# BoardB-FPGA.net
KiCad netlist of a schematic drawn in Altium Designer
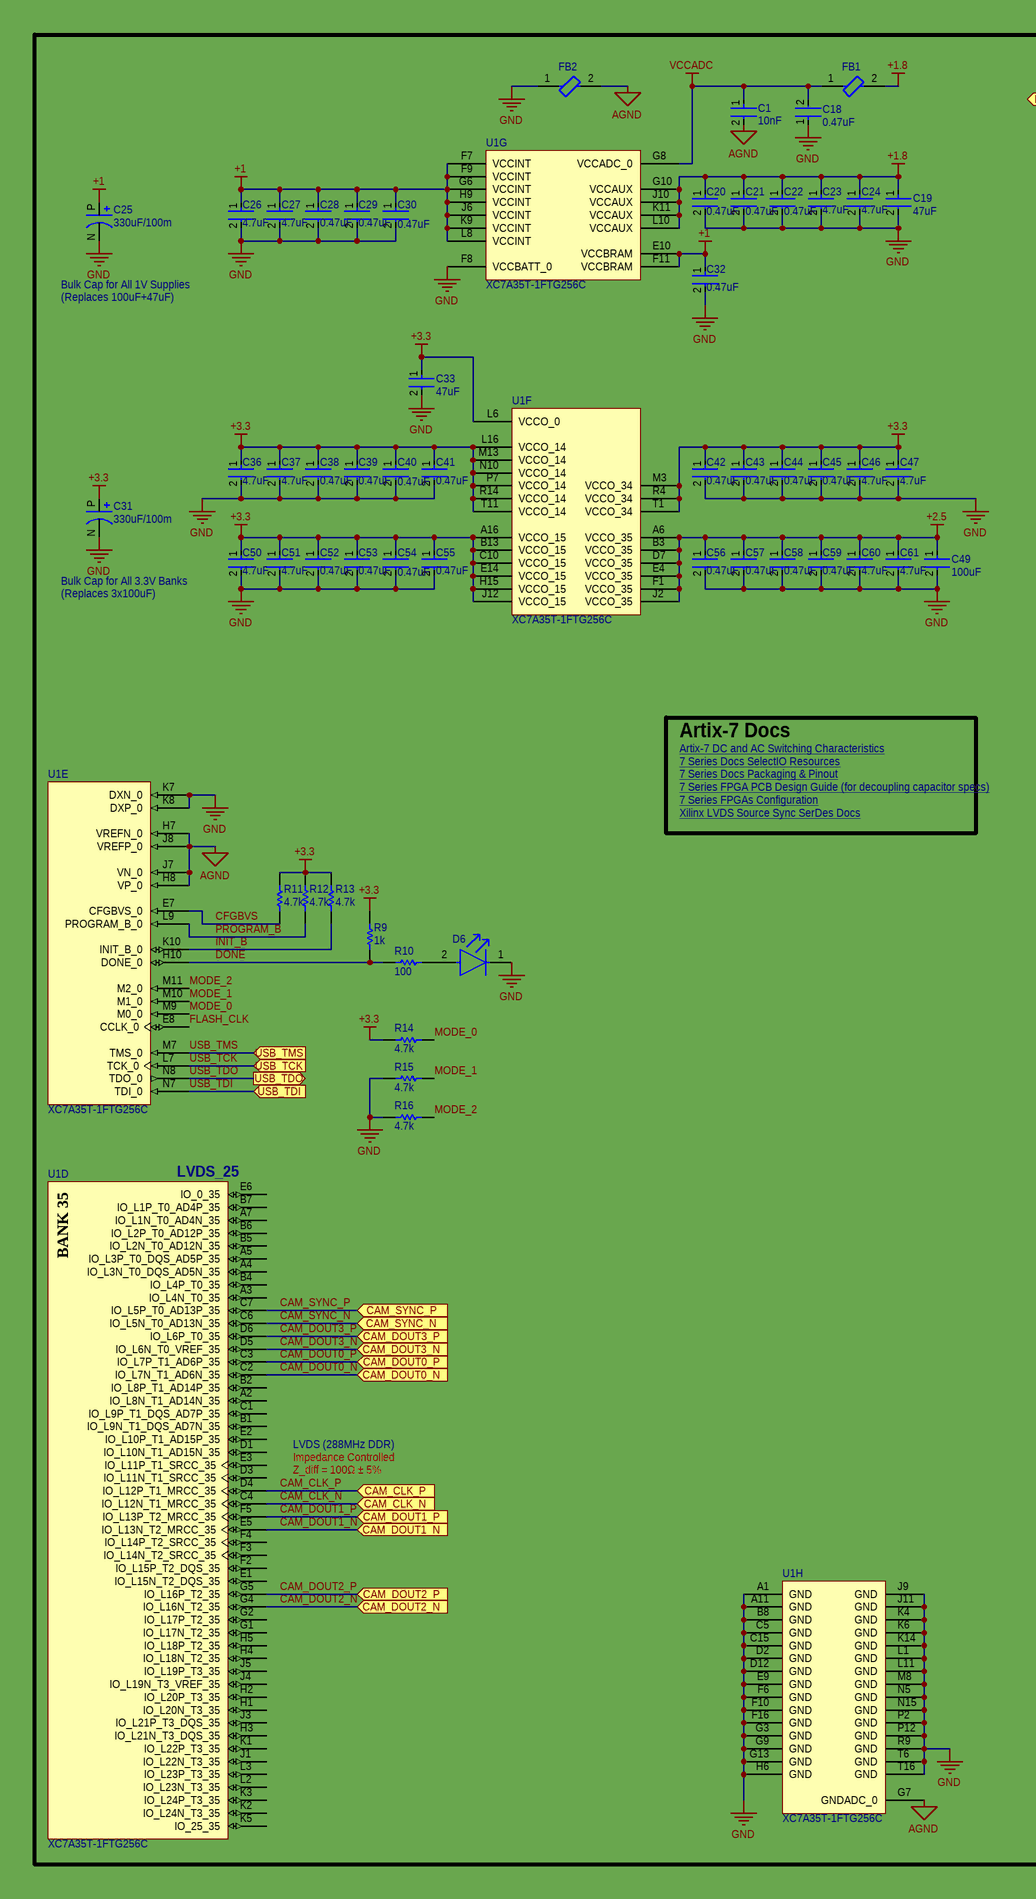
[diagram p0: BoardB-FPGA.SchDoc, left]
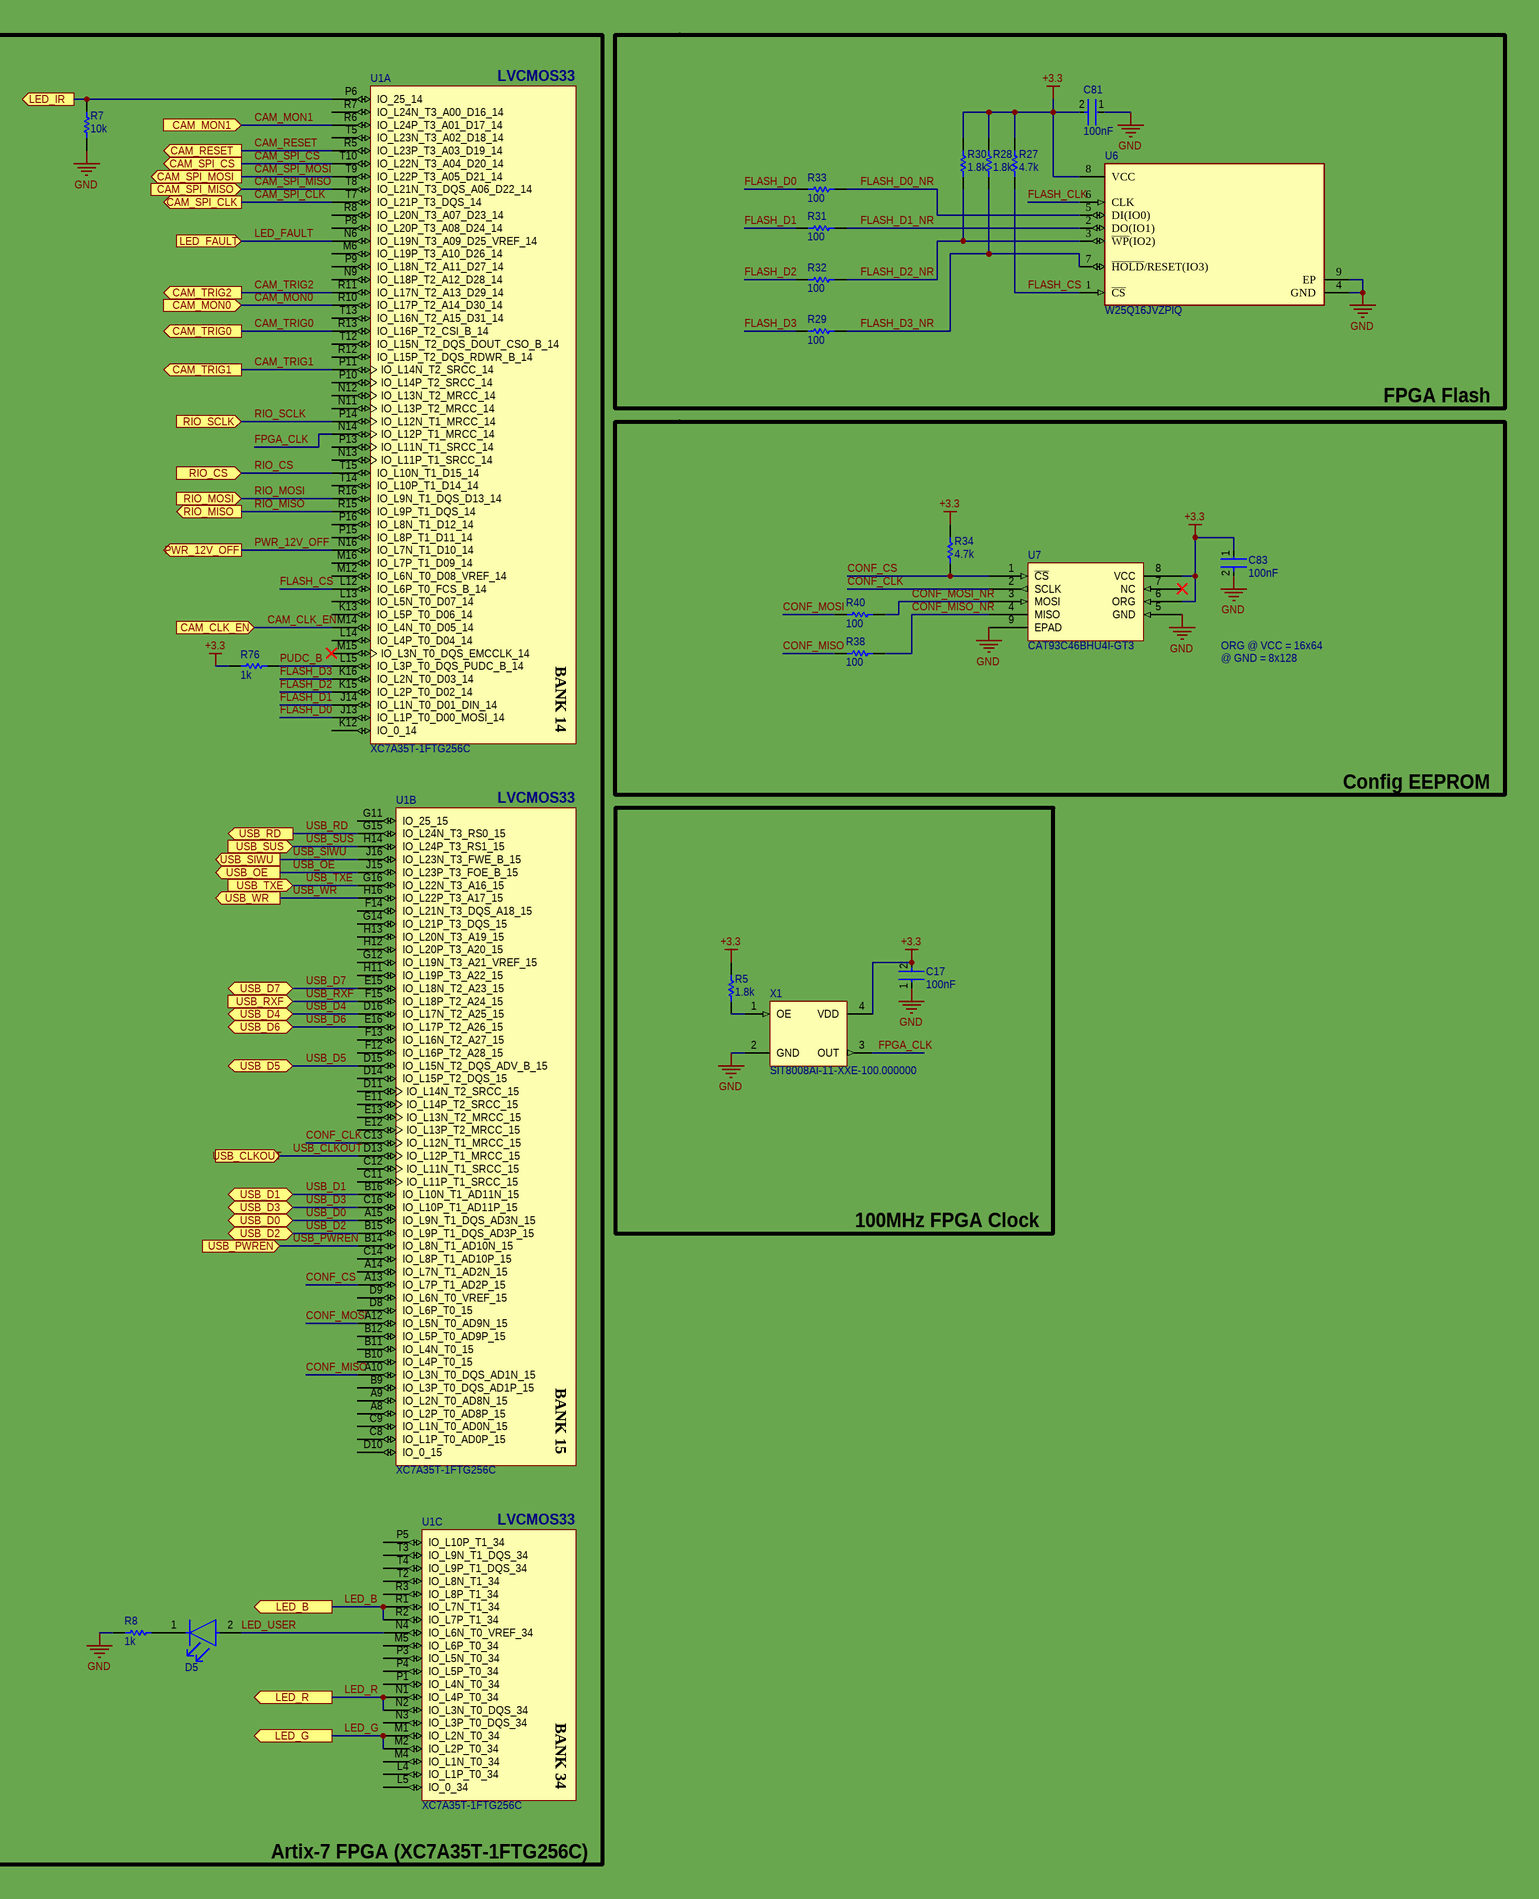
[diagram p1: BoardB-FPGA.SchDoc, right]

(export (version "E")
  (design (tool "Eeschema 10.0.6"))
  (components
    (comp (ref "C1")
      (value "10nF")
      (footprint "FP-GRM033-0_03-IPC_C")
      (description "Chip Multilayer Ceramic Capacitors for General Purpose, 0201, 10000pF, X7R, 15%, 10%, 10V")
      (fields (field (name "VOLTAGE") "10V") (field (name "TOLERANCE") "10%"))
      (libsource (lib "Altium Content Vault") (part "b4654b650e69147ec39a6b967a45e02"))
    )
    (comp (ref "C17")
      (value "100nF")
      (footprint "FP-GRM15-IPC_C")
      (description "CAP CER 0.1UF 16V X7R 0402")
      (fields (field (name "MANUFACTURER PART NUMBER") "GRM155R71C104KA88D") (field (name "TOLERANCE") "10%"))
      (libsource (lib "Altium Content Vault") (part "236180d848d6139a670b325ea6854c9"))
    )
    (comp (ref "C18")
      (value "0.47uF")
      (footprint "FP-GRM033-0_03-IPC_C")
      (description "Chip Multilayer Ceramic Capacitors for General Purpose, 0201, 0.47uF, X5R, 15%, 10%, 6.3V")
      (fields (field (name "TOLERANCE") "10%"))
      (libsource (lib "Altium Content Vault") (part "b4654b650e69147ec39a6b967a45e02"))
    )
    (comp (ref "C19")
      (value "47uF")
      (footprint "FP-GRM188-0_2-MFG")
      (description "Chip Multilayer Ceramic Capacitors for General Purpose, 0603, 47uF, X5R, 15%, 20%, 6.3V")
      (fields (field (name "TOLERANCE") "20%"))
      (libsource (lib "Altium Content Vault") (part "11868f565c42a9108669ba33697ecf6"))
    )
    (comp (ref "C20")
      (value "0.47uF")
      (footprint "FP-GRM033-0_03-IPC_C")
      (description "Chip Multilayer Ceramic Capacitors for General Purpose, 0201, 0.47uF, X5R, 15%, 10%, 6.3V")
      (fields (field (name "TOLERANCE") "10%"))
      (libsource (lib "Altium Content Vault") (part "b4654b650e69147ec39a6b967a45e02"))
    )
    (comp (ref "C21")
      (value "0.47uF")
      (footprint "FP-GRM033-0_03-IPC_C")
      (description "Chip Multilayer Ceramic Capacitors for General Purpose, 0201, 0.47uF, X5R, 15%, 10%, 6.3V")
      (fields (field (name "TOLERANCE") "10%"))
      (libsource (lib "Altium Content Vault") (part "b4654b650e69147ec39a6b967a45e02"))
    )
    (comp (ref "C22")
      (value "0.47uF")
      (footprint "FP-GRM033-0_03-IPC_C")
      (description "Chip Multilayer Ceramic Capacitors for General Purpose, 0201, 0.47uF, X5R, 15%, 10%, 6.3V")
      (fields (field (name "TOLERANCE") "10%"))
      (libsource (lib "Altium Content Vault") (part "b4654b650e69147ec39a6b967a45e02"))
    )
    (comp (ref "C23")
      (value "4.7uF")
      (footprint "FP-GRM155-0_1-IPC_B")
      (description "Chip Multilayer Ceramic Capacitors for General Purpose, 0402, 4.7uF, X5R, 15%, 20%, 6.3V")
      (fields (field (name "VOLTAGE") "6.3V") (field (name "TOLERANCE") "20%"))
      (libsource (lib "Altium Content Vault") (part "11868f565c42a9108669ba33697ecf6"))
    )
    (comp (ref "C24")
      (value "4.7uF")
      (footprint "FP-GRM155-0_1-IPC_B")
      (description "Chip Multilayer Ceramic Capacitors for General Purpose, 0402, 4.7uF, X5R, 15%, 20%, 6.3V")
      (fields (field (name "VOLTAGE") "6.3V") (field (name "TOLERANCE") "20%"))
      (libsource (lib "Altium Content Vault") (part "11868f565c42a9108669ba33697ecf6"))
    )
    (comp (ref "C25")
      (value "330uF/100m")
      (footprint "NOSD337M004R0100")
      (description "330uF +/-20% 4 V dc SMD Niobium Capacitor; 7343-31 package; ESR 0.1Ohms NOS")
      (fields
        (field (name "MANUFACTURER") "Kyocera AVX")
        (field (name "MANUFACTURER PART NUMBER") "NOSD337M004R0100")
      )
      (libsource (lib "Virtex") (part "NOSD337M004R0100"))
    )
    (comp (ref "C26")
      (value "4.7uF")
      (footprint "FP-GRM155-0_1-IPC_B")
      (description "Chip Multilayer Ceramic Capacitors for General Purpose, 0402, 4.7uF, X5R, 15%, 20%, 6.3V")
      (fields (field (name "VOLTAGE") "6.3V") (field (name "TOLERANCE") "20%"))
      (libsource (lib "Altium Content Vault") (part "11868f565c42a9108669ba33697ecf6"))
    )
    (comp (ref "C27")
      (value "4.7uF")
      (footprint "FP-GRM155-0_1-IPC_B")
      (description "Chip Multilayer Ceramic Capacitors for General Purpose, 0402, 4.7uF, X5R, 15%, 20%, 6.3V")
      (fields (field (name "VOLTAGE") "6.3V") (field (name "TOLERANCE") "20%"))
      (libsource (lib "Altium Content Vault") (part "11868f565c42a9108669ba33697ecf6"))
    )
    (comp (ref "C28")
      (value "0.47uF")
      (footprint "FP-GRM033-0_03-IPC_C")
      (description "Chip Multilayer Ceramic Capacitors for General Purpose, 0201, 0.47uF, X5R, 15%, 10%, 6.3V")
      (fields (field (name "TOLERANCE") "10%"))
      (libsource (lib "Altium Content Vault") (part "b4654b650e69147ec39a6b967a45e02"))
    )
    (comp (ref "C29")
      (value "0.47uF")
      (footprint "FP-GRM033-0_03-IPC_C")
      (description "Chip Multilayer Ceramic Capacitors for General Purpose, 0201, 0.47uF, X5R, 15%, 10%, 6.3V")
      (fields (field (name "TOLERANCE") "10%"))
      (libsource (lib "Altium Content Vault") (part "b4654b650e69147ec39a6b967a45e02"))
    )
    (comp (ref "C30")
      (value "0.47uF")
      (footprint "FP-GRM033-0_03-IPC_C")
      (description "Chip Multilayer Ceramic Capacitors for General Purpose, 0201, 0.47uF, X5R, 15%, 10%, 6.3V")
      (fields (field (name "TOLERANCE") "10%"))
      (libsource (lib "Altium Content Vault") (part "b4654b650e69147ec39a6b967a45e02"))
    )
    (comp (ref "C31")
      (value "330uF/100m")
      (footprint "NOSD337M004R0100")
      (description "330uF +/-20% 4 V dc SMD Niobium Capacitor; 7343-31 package; ESR 0.1Ohms NOS")
      (fields
        (field (name "MANUFACTURER") "Kyocera AVX")
        (field (name "MANUFACTURER PART NUMBER") "NOSD337M004R0100")
      )
      (libsource (lib "Virtex") (part "NOSD337M004R0100"))
    )
    (comp (ref "C32")
      (value "0.47uF")
      (footprint "FP-GRM033-0_03-IPC_C")
      (description "Chip Multilayer Ceramic Capacitors for General Purpose, 0201, 0.47uF, X5R, 15%, 10%, 6.3V")
      (fields (field (name "TOLERANCE") "10%"))
      (libsource (lib "Altium Content Vault") (part "b4654b650e69147ec39a6b967a45e02"))
    )
    (comp (ref "C33")
      (value "47uF")
      (footprint "FP-GRM188-0_2-MFG")
      (description "Chip Multilayer Ceramic Capacitors for General Purpose, 0603, 47uF, X5R, 15%, 20%, 6.3V")
      (fields (field (name "TOLERANCE") "20%"))
      (libsource (lib "Altium Content Vault") (part "11868f565c42a9108669ba33697ecf6"))
    )
    (comp (ref "C36")
      (value "4.7uF")
      (footprint "FP-GRM155-0_1-IPC_B")
      (description "Chip Multilayer Ceramic Capacitors for General Purpose, 0402, 4.7uF, X5R, 15%, 20%, 6.3V")
      (fields (field (name "VOLTAGE") "6.3V") (field (name "TOLERANCE") "20%"))
      (libsource (lib "Altium Content Vault") (part "11868f565c42a9108669ba33697ecf6"))
    )
    (comp (ref "C37")
      (value "4.7uF")
      (footprint "FP-GRM155-0_1-IPC_B")
      (description "Chip Multilayer Ceramic Capacitors for General Purpose, 0402, 4.7uF, X5R, 15%, 20%, 6.3V")
      (fields (field (name "VOLTAGE") "6.3V") (field (name "TOLERANCE") "20%"))
      (libsource (lib "Altium Content Vault") (part "11868f565c42a9108669ba33697ecf6"))
    )
    (comp (ref "C38")
      (value "0.47uF")
      (footprint "FP-GRM033-0_03-IPC_C")
      (description "Chip Multilayer Ceramic Capacitors for General Purpose, 0201, 0.47uF, X5R, 15%, 10%, 6.3V")
      (fields (field (name "TOLERANCE") "10%"))
      (libsource (lib "Altium Content Vault") (part "b4654b650e69147ec39a6b967a45e02"))
    )
    (comp (ref "C39")
      (value "0.47uF")
      (footprint "FP-GRM033-0_03-IPC_C")
      (description "Chip Multilayer Ceramic Capacitors for General Purpose, 0201, 0.47uF, X5R, 15%, 10%, 6.3V")
      (fields (field (name "TOLERANCE") "10%"))
      (libsource (lib "Altium Content Vault") (part "b4654b650e69147ec39a6b967a45e02"))
    )
    (comp (ref "C40")
      (value "0.47uF")
      (footprint "FP-GRM033-0_03-IPC_C")
      (description "Chip Multilayer Ceramic Capacitors for General Purpose, 0201, 0.47uF, X5R, 15%, 10%, 6.3V")
      (fields (field (name "TOLERANCE") "10%"))
      (libsource (lib "Altium Content Vault") (part "b4654b650e69147ec39a6b967a45e02"))
    )
    (comp (ref "C41")
      (value "0.47uF")
      (footprint "FP-GRM033-0_03-IPC_C")
      (description "Chip Multilayer Ceramic Capacitors for General Purpose, 0201, 0.47uF, X5R, 15%, 10%, 6.3V")
      (fields (field (name "TOLERANCE") "10%"))
      (libsource (lib "Altium Content Vault") (part "b4654b650e69147ec39a6b967a45e02"))
    )
    (comp (ref "C42")
      (value "0.47uF")
      (footprint "FP-GRM033-0_03-IPC_C")
      (description "Chip Multilayer Ceramic Capacitors for General Purpose, 0201, 0.47uF, X5R, 15%, 10%, 6.3V")
      (fields (field (name "TOLERANCE") "10%"))
      (libsource (lib "Altium Content Vault") (part "b4654b650e69147ec39a6b967a45e02"))
    )
    (comp (ref "C43")
      (value "0.47uF")
      (footprint "FP-GRM033-0_03-IPC_C")
      (description "Chip Multilayer Ceramic Capacitors for General Purpose, 0201, 0.47uF, X5R, 15%, 10%, 6.3V")
      (fields (field (name "TOLERANCE") "10%"))
      (libsource (lib "Altium Content Vault") (part "b4654b650e69147ec39a6b967a45e02"))
    )
    (comp (ref "C44")
      (value "0.47uF")
      (footprint "FP-GRM033-0_03-IPC_C")
      (description "Chip Multilayer Ceramic Capacitors for General Purpose, 0201, 0.47uF, X5R, 15%, 10%, 6.3V")
      (fields (field (name "TOLERANCE") "10%"))
      (libsource (lib "Altium Content Vault") (part "b4654b650e69147ec39a6b967a45e02"))
    )
    (comp (ref "C45")
      (value "0.47uF")
      (footprint "FP-GRM033-0_03-IPC_C")
      (description "Chip Multilayer Ceramic Capacitors for General Purpose, 0201, 0.47uF, X5R, 15%, 10%, 6.3V")
      (fields (field (name "TOLERANCE") "10%"))
      (libsource (lib "Altium Content Vault") (part "b4654b650e69147ec39a6b967a45e02"))
    )
    (comp (ref "C46")
      (value "4.7uF")
      (footprint "FP-GRM155-0_1-IPC_B")
      (description "Chip Multilayer Ceramic Capacitors for General Purpose, 0402, 4.7uF, X5R, 15%, 20%, 6.3V")
      (fields (field (name "VOLTAGE") "6.3V") (field (name "TOLERANCE") "20%"))
      (libsource (lib "Altium Content Vault") (part "11868f565c42a9108669ba33697ecf6"))
    )
    (comp (ref "C47")
      (value "4.7uF")
      (footprint "FP-GRM155-0_1-IPC_B")
      (description "Chip Multilayer Ceramic Capacitors for General Purpose, 0402, 4.7uF, X5R, 15%, 20%, 6.3V")
      (fields (field (name "VOLTAGE") "6.3V") (field (name "TOLERANCE") "20%"))
      (libsource (lib "Altium Content Vault") (part "11868f565c42a9108669ba33697ecf6"))
    )
    (comp (ref "C49")
      (value "100uF")
      (footprint "FP-GRM21B-0_2-e0_2_0_7-MFG")
      (description "Chip Multilayer Ceramic Capacitors for General Purpose, 0805, 100uF, X5R, 15%, 20%, 6.3V")
      (fields (field (name "TOLERANCE") "20%"))
      (libsource (lib "Altium Content Vault") (part "b4654b650e69147ec39a6b967a45e02"))
    )
    (comp (ref "C50")
      (value "4.7uF")
      (footprint "FP-GRM155-0_1-IPC_B")
      (description "Chip Multilayer Ceramic Capacitors for General Purpose, 0402, 4.7uF, X5R, 15%, 20%, 6.3V")
      (fields (field (name "VOLTAGE") "6.3V") (field (name "TOLERANCE") "20%"))
      (libsource (lib "Altium Content Vault") (part "11868f565c42a9108669ba33697ecf6"))
    )
    (comp (ref "C51")
      (value "4.7uF")
      (footprint "FP-GRM155-0_1-IPC_B")
      (description "Chip Multilayer Ceramic Capacitors for General Purpose, 0402, 4.7uF, X5R, 15%, 20%, 6.3V")
      (fields (field (name "VOLTAGE") "6.3V") (field (name "TOLERANCE") "20%"))
      (libsource (lib "Altium Content Vault") (part "11868f565c42a9108669ba33697ecf6"))
    )
    (comp (ref "C52")
      (value "0.47uF")
      (footprint "FP-GRM033-0_03-IPC_C")
      (description "Chip Multilayer Ceramic Capacitors for General Purpose, 0201, 0.47uF, X5R, 15%, 10%, 6.3V")
      (fields (field (name "TOLERANCE") "10%"))
      (libsource (lib "Altium Content Vault") (part "b4654b650e69147ec39a6b967a45e02"))
    )
    (comp (ref "C53")
      (value "0.47uF")
      (footprint "FP-GRM033-0_03-IPC_C")
      (description "Chip Multilayer Ceramic Capacitors for General Purpose, 0201, 0.47uF, X5R, 15%, 10%, 6.3V")
      (fields (field (name "TOLERANCE") "10%"))
      (libsource (lib "Altium Content Vault") (part "b4654b650e69147ec39a6b967a45e02"))
    )
    (comp (ref "C54")
      (value "0.47uF")
      (footprint "FP-GRM033-0_03-IPC_C")
      (description "Chip Multilayer Ceramic Capacitors for General Purpose, 0201, 0.47uF, X5R, 15%, 10%, 6.3V")
      (fields (field (name "TOLERANCE") "10%"))
      (libsource (lib "Altium Content Vault") (part "b4654b650e69147ec39a6b967a45e02"))
    )
    (comp (ref "C55")
      (value "0.47uF")
      (footprint "FP-GRM033-0_03-IPC_C")
      (description "Chip Multilayer Ceramic Capacitors for General Purpose, 0201, 0.47uF, X5R, 15%, 10%, 6.3V")
      (fields (field (name "TOLERANCE") "10%"))
      (libsource (lib "Altium Content Vault") (part "b4654b650e69147ec39a6b967a45e02"))
    )
    (comp (ref "C56")
      (value "0.47uF")
      (footprint "FP-GRM033-0_03-IPC_C")
      (description "Chip Multilayer Ceramic Capacitors for General Purpose, 0201, 0.47uF, X5R, 15%, 10%, 6.3V")
      (fields (field (name "TOLERANCE") "10%"))
      (libsource (lib "Altium Content Vault") (part "b4654b650e69147ec39a6b967a45e02"))
    )
    (comp (ref "C57")
      (value "0.47uF")
      (footprint "FP-GRM033-0_03-IPC_C")
      (description "Chip Multilayer Ceramic Capacitors for General Purpose, 0201, 0.47uF, X5R, 15%, 10%, 6.3V")
      (fields (field (name "TOLERANCE") "10%"))
      (libsource (lib "Altium Content Vault") (part "b4654b650e69147ec39a6b967a45e02"))
    )
    (comp (ref "C58")
      (value "0.47uF")
      (footprint "FP-GRM033-0_03-IPC_C")
      (description "Chip Multilayer Ceramic Capacitors for General Purpose, 0201, 0.47uF, X5R, 15%, 10%, 6.3V")
      (fields (field (name "TOLERANCE") "10%"))
      (libsource (lib "Altium Content Vault") (part "b4654b650e69147ec39a6b967a45e02"))
    )
    (comp (ref "C59")
      (value "0.47uF")
      (footprint "FP-GRM033-0_03-IPC_C")
      (description "Chip Multilayer Ceramic Capacitors for General Purpose, 0201, 0.47uF, X5R, 15%, 10%, 6.3V")
      (fields (field (name "TOLERANCE") "10%"))
      (libsource (lib "Altium Content Vault") (part "b4654b650e69147ec39a6b967a45e02"))
    )
    (comp (ref "C60")
      (value "4.7uF")
      (footprint "FP-GRM155-0_1-IPC_B")
      (description "Chip Multilayer Ceramic Capacitors for General Purpose, 0402, 4.7uF, X5R, 15%, 20%, 6.3V")
      (fields (field (name "VOLTAGE") "6.3V") (field (name "TOLERANCE") "20%"))
      (libsource (lib "Altium Content Vault") (part "11868f565c42a9108669ba33697ecf6"))
    )
    (comp (ref "C61")
      (value "4.7uF")
      (footprint "FP-GRM155-0_1-IPC_B")
      (description "Chip Multilayer Ceramic Capacitors for General Purpose, 0402, 4.7uF, X5R, 15%, 20%, 6.3V")
      (fields (field (name "VOLTAGE") "6.3V") (field (name "TOLERANCE") "20%"))
      (libsource (lib "Altium Content Vault") (part "11868f565c42a9108669ba33697ecf6"))
    )
    (comp (ref "C81")
      (value "100nF")
      (footprint "FP-GRM15-MFG")
      (description "CAP CER 0.1UF 16V X7R 0402")
      (fields (field (name "MANUFACTURER PART NUMBER") "GRM155R71C104KA88D") (field (name "TOLERANCE") "10%"))
      (libsource (lib "Altium Content Vault") (part "236180d848d6139a670b325ea6854c9"))
    )
    (comp (ref "C83")
      (value "100nF")
      (footprint "FP-GRM15-MFG")
      (description "CAP CER 0.1UF 16V X7R 0402")
      (fields (field (name "MANUFACTURER PART NUMBER") "GRM155R71C104KA88D") (field (name "TOLERANCE") "10%"))
      (libsource (lib "Altium Content Vault") (part "236180d848d6139a670b325ea6854c9"))
    )
    (comp (ref "D5")
      (value "SML-D12U1WT86")
      (footprint "FP-SML-D12-MFG")
      (description "LED RED DIFFUSED 1608 SMD")
      (fields
        (field (name "MANUFACTURER") "Rohm")
        (field (name "OCTOPART") "https://octopart.com/sml-d12u1wt86-rohm-70850259")
      )
      (libsource (lib "Altium Content Vault") (part "8706943c75ba83719d021d2fdc84c58"))
    )
    (comp (ref "D6")
      (value "SML-D12U1WT86")
      (footprint "FP-SML-D12-MFG")
      (description "LED RED DIFFUSED 1608 SMD")
      (fields
        (field (name "MANUFACTURER") "Rohm")
        (field (name "OCTOPART") "https://octopart.com/sml-d12u1wt86-rohm-70850259")
      )
      (libsource (lib "Altium Content Vault") (part "8706943c75ba83719d021d2fdc84c58"))
    )
    (comp (ref "FB1")
      (value "BLM18AG601SN1D")
      (footprint "FP-BLM18-0_15-t0_8-MFG")
      (description "Chip Ferrite Bead, 0603, 600Ω @ 100MHz, 0.38Ω, 25%, 500mA")
      (fields (field (name "TOLERANCE") "25%"))
      (libsource (lib "Altium Content Vault") (part "5f30dd21d616792df468990f7003faa"))
    )
    (comp (ref "FB2")
      (value "BLM18AG601SN1D")
      (footprint "FP-BLM18-0_15-t0_8-MFG")
      (description "Chip Ferrite Bead, 0603, 600Ω @ 100MHz, 0.38Ω, 25%, 500mA")
      (fields (field (name "TOLERANCE") "25%"))
      (libsource (lib "Altium Content Vault") (part "5f30dd21d616792df468990f7003faa"))
    )
    (comp (ref "R5")
      (value "1.8k")
      (footprint "RESC1005X40X25LL05T05")
      (fields (field (name "MANUFACTURER") "Panasonic") (field (name "PART NUMBER") "ERJ2RKF1801X"))
      (libsource (lib "Altium Content Vault") (part "RES"))
    )
    (comp (ref "R7")
      (value "10k")
      (footprint "RESC1005X40X25LL05T05")
      (description "Chip Resistor, 10 KOhm, +/- 1%, 0.1 W, -55 to 155 degC, 0402 (1005 Metric), RoHS, Tape and Reel")
      (fields (field (name "TOLERANCE") "1%") (field (name "MANUFACTURER") "Panasonic"))
      (libsource (lib "Altium Content Vault") (part "RES-2"))
    )
    (comp (ref "R8")
      (value "1k")
      (footprint "RESC1005X40X25NL05T05")
      (description "Chip Resistor, 1 KOhm, +/- 1%, 100 mW, -55 to 155 degC, 0402 (1005 Metric), RoHS, Tape and Reel")
      (fields (field (name "PARTNUMBER") "ERJ-2RKF1001X") (field (name "MANUFACTURER") "Basic Passives"))
      (libsource (lib "Altium Content Vault") (part "RES-2"))
    )
    (comp (ref "R9")
      (value "1k")
      (footprint "RESC1005X40X25NL05T05")
      (description "Chip Resistor, 1 KOhm, +/- 1%, 100 mW, -55 to 155 degC, 0402 (1005 Metric), RoHS, Tape and Reel")
      (fields (field (name "PARTNUMBER") "ERJ-2RKF1001X") (field (name "MANUFACTURER") "Basic Passives"))
      (libsource (lib "Altium Content Vault") (part "RES-2"))
    )
    (comp (ref "R10")
      (value "100")
      (footprint "RESC1005X40X25LL05T05")
      (description "Chip Resistor, 100 Ohm, +/- 1%, 100 mW, -55 to 155 degC, 0402 (1005 Metric), RoHS, Tape and Reel")
      (fields (field (name "MANUFACTURER") "Basic Passives") (field (name "TOLERANCE") "1%"))
      (libsource (lib "Altium Content Vault") (part "RES-2"))
    )
    (comp (ref "R11")
      (value "4.7k")
      (footprint "RESC1005X40X25LL05T05")
      (description "Chip Resistor, 4.7 KOhm, +/- 1%, 0.1 W, -55 to 155 degC, 0402 (1005 Metric), RoHS, Tape and Reel")
      (fields (field (name "TOLERANCE") "1%") (field (name "PARTNUMBER") "ERJ-2RKF4701X"))
      (libsource (lib "Altium Content Vault") (part "RES-2"))
    )
    (comp (ref "R12")
      (value "4.7k")
      (footprint "RESC1005X40X25LL05T05")
      (description "Chip Resistor, 4.7 KOhm, +/- 1%, 0.1 W, -55 to 155 degC, 0402 (1005 Metric), RoHS, Tape and Reel")
      (fields (field (name "TOLERANCE") "1%") (field (name "PARTNUMBER") "ERJ-2RKF4701X"))
      (libsource (lib "Altium Content Vault") (part "RES-2"))
    )
    (comp (ref "R13")
      (value "4.7k")
      (footprint "RESC1005X40X25LL05T05")
      (description "Chip Resistor, 4.7 KOhm, +/- 1%, 0.1 W, -55 to 155 degC, 0402 (1005 Metric), RoHS, Tape and Reel")
      (fields (field (name "TOLERANCE") "1%") (field (name "PARTNUMBER") "ERJ-2RKF4701X"))
      (libsource (lib "Altium Content Vault") (part "RES-2"))
    )
    (comp (ref "R14")
      (value "4.7k")
      (footprint "RESC1005X40X25LL05T05")
      (description "Chip Resistor, 4.7 KOhm, +/- 1%, 0.1 W, -55 to 155 degC, 0402 (1005 Metric), RoHS, Tape and Reel")
      (fields (field (name "TOLERANCE") "1%") (field (name "PARTNUMBER") "ERJ-2RKF4701X"))
      (libsource (lib "Altium Content Vault") (part "RES-2"))
    )
    (comp (ref "R15")
      (value "4.7k")
      (footprint "RESC1005X40X25LL05T05")
      (description "Chip Resistor, 4.7 KOhm, +/- 1%, 0.1 W, -55 to 155 degC, 0402 (1005 Metric), RoHS, Tape and Reel")
      (fields (field (name "TOLERANCE") "1%") (field (name "PARTNUMBER") "ERJ-2RKF4701X"))
      (libsource (lib "Altium Content Vault") (part "RES-2"))
    )
    (comp (ref "R16")
      (value "4.7k")
      (footprint "RESC1005X40X25LL05T05")
      (description "Chip Resistor, 4.7 KOhm, +/- 1%, 0.1 W, -55 to 155 degC, 0402 (1005 Metric), RoHS, Tape and Reel")
      (fields (field (name "TOLERANCE") "1%") (field (name "PARTNUMBER") "ERJ-2RKF4701X"))
      (libsource (lib "Altium Content Vault") (part "RES-2"))
    )
    (comp (ref "R27")
      (value "4.7k")
      (footprint "RESC1005X40X25NL05T05")
      (description "Chip Resistor, 4.7 KOhm, +/- 1%, 0.1 W, -55 to 155 degC, 0402 (1005 Metric), RoHS, Tape and Reel")
      (fields (field (name "TOLERANCE") "1%") (field (name "PARTNUMBER") "ERJ-2RKF4701X"))
      (libsource (lib "Altium Content Vault") (part "RES-2"))
    )
    (comp (ref "R28")
      (value "1.8k")
      (footprint "RESC1005X40X25LL05T05")
      (fields (field (name "MANUFACTURER") "Panasonic") (field (name "PART NUMBER") "ERJ2RKF1801X"))
      (libsource (lib "Altium Content Vault") (part "RES"))
    )
    (comp (ref "R29")
      (value "100")
      (footprint "RESC1005X40X25LL05T05")
      (description "Chip Resistor, 100 Ohm, +/- 1%, 100 mW, -55 to 155 degC, 0402 (1005 Metric), RoHS, Tape and Reel")
      (fields (field (name "MANUFACTURER") "Basic Passives") (field (name "TOLERANCE") "1%"))
      (libsource (lib "Altium Content Vault") (part "RES-2"))
    )
    (comp (ref "R30")
      (value "1.8k")
      (footprint "RESC1005X40X25LL05T05")
      (fields (field (name "MANUFACTURER") "Panasonic") (field (name "PART NUMBER") "ERJ2RKF1801X"))
      (libsource (lib "Altium Content Vault") (part "RES"))
    )
    (comp (ref "R31")
      (value "100")
      (footprint "RESC1005X40X25LL05T05")
      (description "Chip Resistor, 100 Ohm, +/- 1%, 100 mW, -55 to 155 degC, 0402 (1005 Metric), RoHS, Tape and Reel")
      (fields (field (name "MANUFACTURER") "Basic Passives") (field (name "TOLERANCE") "1%"))
      (libsource (lib "Altium Content Vault") (part "RES-2"))
    )
    (comp (ref "R32")
      (value "100")
      (footprint "RESC1005X40X25LL05T05")
      (description "Chip Resistor, 100 Ohm, +/- 1%, 100 mW, -55 to 155 degC, 0402 (1005 Metric), RoHS, Tape and Reel")
      (fields (field (name "MANUFACTURER") "Basic Passives") (field (name "TOLERANCE") "1%"))
      (libsource (lib "Altium Content Vault") (part "RES-2"))
    )
    (comp (ref "R33")
      (value "100")
      (footprint "RESC1005X40X25LL05T05")
      (description "Chip Resistor, 100 Ohm, +/- 1%, 100 mW, -55 to 155 degC, 0402 (1005 Metric), RoHS, Tape and Reel")
      (fields (field (name "MANUFACTURER") "Basic Passives") (field (name "TOLERANCE") "1%"))
      (libsource (lib "Altium Content Vault") (part "RES-2"))
    )
    (comp (ref "R34")
      (value "4.7k")
      (footprint "RESC1005X40X25NL05T05")
      (description "Chip Resistor, 4.7 KOhm, +/- 1%, 0.1 W, -55 to 155 degC, 0402 (1005 Metric), RoHS, Tape and Reel")
      (fields (field (name "TOLERANCE") "1%") (field (name "PARTNUMBER") "ERJ-2RKF4701X"))
      (libsource (lib "Altium Content Vault") (part "RES-2"))
    )
    (comp (ref "R38")
      (value "100")
      (footprint "RESC1005X40X25LL05T05")
      (description "Chip Resistor, 100 Ohm, +/- 1%, 100 mW, -55 to 155 degC, 0402 (1005 Metric), RoHS, Tape and Reel")
      (fields (field (name "MANUFACTURER") "Basic Passives") (field (name "TOLERANCE") "1%"))
      (libsource (lib "Altium Content Vault") (part "RES-2"))
    )
    (comp (ref "R40")
      (value "100")
      (footprint "RESC1005X40X25LL05T05")
      (description "Chip Resistor, 100 Ohm, +/- 1%, 100 mW, -55 to 155 degC, 0402 (1005 Metric), RoHS, Tape and Reel")
      (fields (field (name "MANUFACTURER") "Basic Passives") (field (name "TOLERANCE") "1%"))
      (libsource (lib "Altium Content Vault") (part "RES-2"))
    )
    (comp (ref "R76")
      (value "1k")
      (footprint "RESC0603X26X15LL03T05")
      (fields (field (name "MANUFACTURER") "Panasonic") (field (name "PART NUMBER") "ERJ1GNF1001C"))
      (libsource (lib "Altium Content Vault") (part "RES"))
    )
    (comp (ref "U1")
      (value "XC7A35T-1FTG256C")
      (footprint "FTG256")
      (description "Artix-7 FPGA, 170 User I/Os, 0 GTP, 256-Ball BGA, Speed Grade 1, Commercial Grade, Pb-Free")
      (fields (field (name "MANUFACTURER") "Xilinx"))
      (libsource (lib "Altium Content Vault") (part "XLNX-XC7A35T-FTG256"))
    )
    (comp (ref "U6")
      (value "W25Q16JVZPIQ")
      (footprint "FP-ZP-IPC_B")
      (description "IC FLASH 16MBIT SPI/QUAD 8WSON")
      (libsource (lib "Altium Content Vault") (part "4cb77c13ae9adfb05a25f85e82aeb43"))
    )
    (comp (ref "U7")
      (value "CAT93C46BHU4I-GT3")
      (footprint "CAT93C46BHU4I-GT3")
      (description "EEPROM Memory IC 1Kb (128 x 8, 64 x 16) SPI 4 MHz 8-UDFN-EP (2x3)")
      (libsource (lib "Virtex") (part "CAT93C46BHU4I-GT3"))
    )
    (comp (ref "X1")
      (value "SIT8008AI-11-XXE-100.000000")
      (footprint "SIT8008AI-11-XXE-100.000000")
      (fields
        (field (name "MANUFACTURER") "SiTime")
        (field (name "MANUFACTURER PART NUMBER") "SIT8008AI-11-XXE-100.000000E")
      )
      (libsource (lib "Virtex") (part "SIT8008AI-11-XXE-100.000000"))
    )
  )
  (nets
    (net (code "1") (name "+1") (class "Default")
      (node (ref "C25") (pin "P") (pintype "passive"))
      (node (ref "C26") (pin "1") (pinfunction "1_1") (pintype "passive"))
      (node (ref "C27") (pin "1") (pinfunction "1_1") (pintype "passive"))
      (node (ref "C28") (pin "1") (pinfunction "1_1") (pintype "passive"))
      (node (ref "C29") (pin "1") (pinfunction "1_1") (pintype "passive"))
      (node (ref "C30") (pin "1") (pinfunction "1_1") (pintype "passive"))
      (node (ref "C32") (pin "1") (pinfunction "1_1") (pintype "passive"))
      (node (ref "U1") (pin "E10") (pinfunction "VCCBRAM_E10") (pintype "power_in"))
      (node (ref "U1") (pin "F11") (pinfunction "VCCBRAM_F11") (pintype "power_in"))
      (node (ref "U1") (pin "F7") (pinfunction "VCCINT_F7") (pintype "power_in"))
      (node (ref "U1") (pin "F9") (pinfunction "VCCINT_F9") (pintype "power_in"))
      (node (ref "U1") (pin "G6") (pinfunction "VCCINT_G6") (pintype "power_in"))
      (node (ref "U1") (pin "H9") (pinfunction "VCCINT_H9") (pintype "power_in"))
      (node (ref "U1") (pin "J6") (pinfunction "VCCINT_J6") (pintype "power_in"))
      (node (ref "U1") (pin "K9") (pinfunction "VCCINT_K9") (pintype "power_in"))
      (node (ref "U1") (pin "L8") (pinfunction "VCCINT_L8") (pintype "power_in"))
    )
    (net (code "2") (name "+1.8") (class "Default")
      (node (ref "C19") (pin "1") (pinfunction "1_1") (pintype "passive"))
      (node (ref "C20") (pin "1") (pinfunction "1_1") (pintype "passive"))
      (node (ref "C21") (pin "1") (pinfunction "1_1") (pintype "passive"))
      (node (ref "C22") (pin "1") (pinfunction "1_1") (pintype "passive"))
      (node (ref "C23") (pin "1") (pinfunction "1_1") (pintype "passive"))
      (node (ref "C24") (pin "1") (pinfunction "1_1") (pintype "passive"))
      (node (ref "FB1") (pin "2") (pinfunction "2_2") (pintype "passive"))
      (node (ref "U1") (pin "G10") (pinfunction "VCCAUX_G10") (pintype "power_in"))
      (node (ref "U1") (pin "J10") (pinfunction "VCCAUX_J10") (pintype "power_in"))
      (node (ref "U1") (pin "K11") (pinfunction "VCCAUX_K11") (pintype "power_in"))
      (node (ref "U1") (pin "L10") (pinfunction "VCCAUX_L10") (pintype "power_in"))
    )
    (net (code "3") (name "+2.5") (class "Default")
      (node (ref "C49") (pin "1") (pinfunction "1_1") (pintype "passive"))
      (node (ref "C56") (pin "1") (pinfunction "1_1") (pintype "passive"))
      (node (ref "C57") (pin "1") (pinfunction "1_1") (pintype "passive"))
      (node (ref "C58") (pin "1") (pinfunction "1_1") (pintype "passive"))
      (node (ref "C59") (pin "1") (pinfunction "1_1") (pintype "passive"))
      (node (ref "C60") (pin "1") (pinfunction "1_1") (pintype "passive"))
      (node (ref "C61") (pin "1") (pinfunction "1_1") (pintype "passive"))
      (node (ref "U1") (pin "A6") (pinfunction "VCCO_35_A6") (pintype "power_in"))
      (node (ref "U1") (pin "B3") (pinfunction "VCCO_35_B3") (pintype "power_in"))
      (node (ref "U1") (pin "D7") (pinfunction "VCCO_35_D7") (pintype "power_in"))
      (node (ref "U1") (pin "E4") (pinfunction "VCCO_35_E4") (pintype "power_in"))
      (node (ref "U1") (pin "F1") (pinfunction "VCCO_35_F1") (pintype "power_in"))
      (node (ref "U1") (pin "J2") (pinfunction "VCCO_35_J2") (pintype "power_in"))
    )
    (net (code "4") (name "+3.3") (class "Default")
      (node (ref "C17") (pin "2") (pinfunction "2_2") (pintype "passive"))
      (node (ref "C31") (pin "P") (pintype "passive"))
      (node (ref "C33") (pin "1") (pinfunction "1_1") (pintype "passive"))
      (node (ref "C36") (pin "1") (pinfunction "1_1") (pintype "passive"))
      (node (ref "C37") (pin "1") (pinfunction "1_1") (pintype "passive"))
      (node (ref "C38") (pin "1") (pinfunction "1_1") (pintype "passive"))
      (node (ref "C39") (pin "1") (pinfunction "1_1") (pintype "passive"))
      (node (ref "C40") (pin "1") (pinfunction "1_1") (pintype "passive"))
      (node (ref "C41") (pin "1") (pinfunction "1_1") (pintype "passive"))
      (node (ref "C42") (pin "1") (pinfunction "1_1") (pintype "passive"))
      (node (ref "C43") (pin "1") (pinfunction "1_1") (pintype "passive"))
      (node (ref "C44") (pin "1") (pinfunction "1_1") (pintype "passive"))
      (node (ref "C45") (pin "1") (pinfunction "1_1") (pintype "passive"))
      (node (ref "C46") (pin "1") (pinfunction "1_1") (pintype "passive"))
      (node (ref "C47") (pin "1") (pinfunction "1_1") (pintype "passive"))
      (node (ref "C50") (pin "1") (pinfunction "1_1") (pintype "passive"))
      (node (ref "C51") (pin "1") (pinfunction "1_1") (pintype "passive"))
      (node (ref "C52") (pin "1") (pinfunction "1_1") (pintype "passive"))
      (node (ref "C53") (pin "1") (pinfunction "1_1") (pintype "passive"))
      (node (ref "C54") (pin "1") (pinfunction "1_1") (pintype "passive"))
      (node (ref "C55") (pin "1") (pinfunction "1_1") (pintype "passive"))
      (node (ref "C81") (pin "2") (pinfunction "2_2") (pintype "passive"))
      (node (ref "C83") (pin "1") (pinfunction "1_1") (pintype "passive"))
      (node (ref "R11") (pin "2") (pinfunction "2_2") (pintype "passive"))
      (node (ref "R12") (pin "2") (pinfunction "2_2") (pintype "passive"))
      (node (ref "R13") (pin "2") (pinfunction "2_2") (pintype "passive"))
      (node (ref "R14") (pin "1") (pinfunction "1_1") (pintype "passive"))
      (node (ref "R27") (pin "2") (pinfunction "2_2") (pintype "passive"))
      (node (ref "R28") (pin "2") (pinfunction "2_2") (pintype "passive"))
      (node (ref "R30") (pin "2") (pinfunction "2_2") (pintype "passive"))
      (node (ref "R34") (pin "2") (pinfunction "2_2") (pintype "passive"))
      (node (ref "R5") (pin "2") (pinfunction "2_2") (pintype "passive"))
      (node (ref "R76") (pin "2") (pinfunction "2_2") (pintype "passive"))
      (node (ref "R9") (pin "1") (pinfunction "1_1") (pintype "passive"))
      (node (ref "U1") (pin "A16") (pinfunction "VCCO_15_A16") (pintype "power_in"))
      (node (ref "U1") (pin "B13") (pinfunction "VCCO_15_B13") (pintype "power_in"))
      (node (ref "U1") (pin "C10") (pinfunction "VCCO_15_C10") (pintype "power_in"))
      (node (ref "U1") (pin "E14") (pinfunction "VCCO_15_E14") (pintype "power_in"))
      (node (ref "U1") (pin "H15") (pinfunction "VCCO_15_H15") (pintype "power_in"))
      (node (ref "U1") (pin "J12") (pinfunction "VCCO_15_J12") (pintype "power_in"))
      (node (ref "U1") (pin "L16") (pinfunction "VCCO_14_L16") (pintype "power_in"))
      (node (ref "U1") (pin "L6") (pinfunction "VCCO_0_L6") (pintype "power_in"))
      (node (ref "U1") (pin "M13") (pinfunction "VCCO_14_M13") (pintype "power_in"))
      (node (ref "U1") (pin "M3") (pinfunction "VCCO_34_M3") (pintype "power_in"))
      (node (ref "U1") (pin "N10") (pinfunction "VCCO_14_N10") (pintype "power_in"))
      (node (ref "U1") (pin "P7") (pinfunction "VCCO_14_P7") (pintype "power_in"))
      (node (ref "U1") (pin "R14") (pinfunction "VCCO_14_R14") (pintype "power_in"))
      (node (ref "U1") (pin "R4") (pinfunction "VCCO_34_R4") (pintype "power_in"))
      (node (ref "U1") (pin "T1") (pinfunction "VCCO_34_T1") (pintype "power_in"))
      (node (ref "U1") (pin "T11") (pinfunction "VCCO_14_T11") (pintype "power_in"))
      (node (ref "U6") (pin "8") (pinfunction "VCC_8") (pintype "power_in"))
      (node (ref "U7") (pin "6") (pinfunction "ORG_6") (pintype "input"))
      (node (ref "U7") (pin "8") (pinfunction "VCC_8") (pintype "power_in"))
      (node (ref "X1") (pin "4") (pinfunction "VDD_4") (pintype "power_in"))
    )
    (net (code "5") (name "/CAM_CLK_EN") (class "Default")
      (node (ref "U1") (pin "M14") (pinfunction "IO_L4N_T0_D05_14_M14") (pintype "bidirectional"))
    )
    (net (code "6") (name "/CAM_CLK_N") (class "Default")
      (node (ref "U1") (pin "C4") (pinfunction "IO_L12N_T1_MRCC_35_C4") (pintype "bidirectional"))
    )
    (net (code "7") (name "/CAM_CLK_P") (class "Default")
      (node (ref "U1") (pin "D4") (pinfunction "IO_L12P_T1_MRCC_35_D4") (pintype "bidirectional"))
    )
    (net (code "8") (name "/CAM_DOUT0_N") (class "Default")
      (node (ref "U1") (pin "C2") (pinfunction "IO_L7N_T1_AD6N_35_C2") (pintype "bidirectional"))
    )
    (net (code "9") (name "/CAM_DOUT0_P") (class "Default")
      (node (ref "U1") (pin "C3") (pinfunction "IO_L7P_T1_AD6P_35_C3") (pintype "bidirectional"))
    )
    (net (code "10") (name "/CAM_DOUT1_N") (class "Default")
      (node (ref "U1") (pin "E5") (pinfunction "IO_L13N_T2_MRCC_35_E5") (pintype "bidirectional"))
    )
    (net (code "11") (name "/CAM_DOUT1_P") (class "Default")
      (node (ref "U1") (pin "F5") (pinfunction "IO_L13P_T2_MRCC_35_F5") (pintype "bidirectional"))
    )
    (net (code "12") (name "/CAM_DOUT2_N") (class "Default")
      (node (ref "U1") (pin "G4") (pinfunction "IO_L16N_T2_35_G4") (pintype "bidirectional"))
    )
    (net (code "13") (name "/CAM_DOUT2_P") (class "Default")
      (node (ref "U1") (pin "G5") (pinfunction "IO_L16P_T2_35_G5") (pintype "bidirectional"))
    )
    (net (code "14") (name "/CAM_DOUT3_N") (class "Default")
      (node (ref "U1") (pin "D5") (pinfunction "IO_L6N_T0_VREF_35_D5") (pintype "bidirectional"))
    )
    (net (code "15") (name "/CAM_DOUT3_P") (class "Default")
      (node (ref "U1") (pin "D6") (pinfunction "IO_L6P_T0_35_D6") (pintype "bidirectional"))
    )
    (net (code "16") (name "/CAM_MON0") (class "Default")
      (node (ref "U1") (pin "R10") (pinfunction "IO_L17P_T2_A14_D30_14_R10") (pintype "bidirectional"))
    )
    (net (code "17") (name "/CAM_MON1") (class "Default")
      (node (ref "U1") (pin "R6") (pinfunction "IO_L24P_T3_A01_D17_14_R6") (pintype "bidirectional"))
    )
    (net (code "18") (name "/CAM_RESET") (class "Default")
      (node (ref "U1") (pin "R5") (pinfunction "IO_L23P_T3_A03_D19_14_R5") (pintype "bidirectional"))
    )
    (net (code "19") (name "/CAM_SPI_CLK") (class "Default")
      (node (ref "U1") (pin "T7") (pinfunction "IO_L21P_T3_DQS_14_T7") (pintype "bidirectional"))
    )
    (net (code "20") (name "/CAM_SPI_CS") (class "Default")
      (node (ref "U1") (pin "T10") (pinfunction "IO_L22N_T3_A04_D20_14_T10") (pintype "bidirectional"))
    )
    (net (code "21") (name "/CAM_SPI_MISO") (class "Default")
      (node (ref "U1") (pin "T8") (pinfunction "IO_L21N_T3_DQS_A06_D22_14_T8") (pintype "bidirectional"))
    )
    (net (code "22") (name "/CAM_SPI_MOSI") (class "Default")
      (node (ref "U1") (pin "T9") (pinfunction "IO_L22P_T3_A05_D21_14_T9") (pintype "bidirectional"))
    )
    (net (code "23") (name "/CAM_SYNC_N") (class "Default")
      (node (ref "U1") (pin "C6") (pinfunction "IO_L5N_T0_AD13N_35_C6") (pintype "bidirectional"))
    )
    (net (code "24") (name "/CAM_SYNC_P") (class "Default")
      (node (ref "U1") (pin "C7") (pinfunction "IO_L5P_T0_AD13P_35_C7") (pintype "bidirectional"))
    )
    (net (code "25") (name "/CAM_TRIG0") (class "Default")
      (node (ref "U1") (pin "R13") (pinfunction "IO_L16P_T2_CSI_B_14_R13") (pintype "bidirectional"))
    )
    (net (code "26") (name "/CAM_TRIG1") (class "Default")
      (node (ref "U1") (pin "P11") (pinfunction "IO_L14N_T2_SRCC_14_P11") (pintype "bidirectional"))
    )
    (net (code "27") (name "/CAM_TRIG2") (class "Default")
      (node (ref "U1") (pin "R11") (pinfunction "IO_L17N_T2_A13_D29_14_R11") (pintype "bidirectional"))
    )
    (net (code "28") (name "/CFGBVS") (class "Default")
      (node (ref "R11") (pin "1") (pinfunction "1_1") (pintype "passive"))
      (node (ref "U1") (pin "E7") (pinfunction "CFGBVS_0_E7") (pintype "input"))
    )
    (net (code "29") (name "/CONF_CLK") (class "Default")
      (node (ref "U1") (pin "C13") (pinfunction "IO_L12N_T1_MRCC_15_C13") (pintype "bidirectional"))
      (node (ref "U7") (pin "2") (pinfunction "SCLK_2") (pintype "output"))
    )
    (net (code "30") (name "/CONF_CS") (class "Default")
      (node (ref "R34") (pin "1") (pinfunction "1_1") (pintype "passive"))
      (node (ref "U1") (pin "A13") (pinfunction "IO_L7P_T1_AD2P_15_A13") (pintype "bidirectional"))
      (node (ref "U7") (pin "1") (pinfunction "~{CS}_1") (pintype "input"))
    )
    (net (code "31") (name "/CONF_MISO") (class "Default")
      (node (ref "R38") (pin "1") (pinfunction "1_1") (pintype "passive"))
      (node (ref "U1") (pin "A10") (pinfunction "IO_L3N_T0_DQS_AD1N_15_A10") (pintype "bidirectional"))
    )
    (net (code "32") (name "/CONF_MISO_NR") (class "Default")
      (node (ref "R38") (pin "2") (pinfunction "2_2") (pintype "passive"))
      (node (ref "U7") (pin "4") (pinfunction "MISO_4") (pintype "power_in"))
    )
    (net (code "33") (name "/CONF_MOSI") (class "Default")
      (node (ref "R40") (pin "1") (pinfunction "1_1") (pintype "passive"))
      (node (ref "U1") (pin "A12") (pinfunction "IO_L5N_T0_AD9N_15_A12") (pintype "bidirectional"))
    )
    (net (code "34") (name "/CONF_MOSI_NR") (class "Default")
      (node (ref "R40") (pin "2") (pinfunction "2_2") (pintype "passive"))
      (node (ref "U7") (pin "3") (pinfunction "MOSI_3") (pintype "input"))
    )
    (net (code "35") (name "/DONE") (class "Default")
      (node (ref "R10") (pin "1") (pinfunction "1_1") (pintype "passive"))
      (node (ref "R9") (pin "2") (pinfunction "2_2") (pintype "passive"))
      (node (ref "U1") (pin "H10") (pinfunction "DONE_0_H10") (pintype "bidirectional"))
    )
    (net (code "36") (name "/FLASH_CLK") (class "Default")
      (node (ref "U1") (pin "E8") (pinfunction "CCLK_0_E8") (pintype "bidirectional"))
      (node (ref "U6") (pin "6") (pinfunction "CLK_6") (pintype "input"))
    )
    (net (code "37") (name "/FLASH_CS") (class "Default")
      (node (ref "R27") (pin "1") (pinfunction "1_1") (pintype "passive"))
      (node (ref "U1") (pin "L12") (pinfunction "IO_L6P_T0_FCS_B_14_L12") (pintype "bidirectional"))
      (node (ref "U6") (pin "1") (pinfunction "~{CS}_1") (pintype "input"))
    )
    (net (code "38") (name "/FLASH_D0") (class "Default")
      (node (ref "R33") (pin "1") (pinfunction "1_1") (pintype "passive"))
      (node (ref "U1") (pin "J13") (pinfunction "IO_L1P_T0_D00_MOSI_14_J13") (pintype "bidirectional"))
    )
    (net (code "39") (name "/FLASH_D0_NR") (class "Default")
      (node (ref "R33") (pin "2") (pinfunction "2_2") (pintype "passive"))
      (node (ref "U6") (pin "5") (pinfunction "DI(IO0)_5") (pintype "bidirectional"))
    )
    (net (code "40") (name "/FLASH_D1") (class "Default")
      (node (ref "R31") (pin "1") (pinfunction "1_1") (pintype "passive"))
      (node (ref "U1") (pin "J14") (pinfunction "IO_L1N_T0_D01_DIN_14_J14") (pintype "bidirectional"))
    )
    (net (code "41") (name "/FLASH_D1_NR") (class "Default")
      (node (ref "R31") (pin "2") (pinfunction "2_2") (pintype "passive"))
      (node (ref "U6") (pin "2") (pinfunction "DO(IO1)_2") (pintype "bidirectional"))
    )
    (net (code "42") (name "/FLASH_D2") (class "Default")
      (node (ref "R32") (pin "1") (pinfunction "1_1") (pintype "passive"))
      (node (ref "U1") (pin "K15") (pinfunction "IO_L2P_T0_D02_14_K15") (pintype "bidirectional"))
    )
    (net (code "43") (name "/FLASH_D2_NR") (class "Default")
      (node (ref "R30") (pin "1") (pinfunction "1_1") (pintype "passive"))
      (node (ref "R32") (pin "2") (pinfunction "2_2") (pintype "passive"))
      (node (ref "U6") (pin "3") (pinfunction "~{WP}(IO2)_3") (pintype "bidirectional"))
    )
    (net (code "44") (name "/FLASH_D3") (class "Default")
      (node (ref "R29") (pin "1") (pinfunction "1_1") (pintype "passive"))
      (node (ref "U1") (pin "K16") (pinfunction "IO_L2N_T0_D03_14_K16") (pintype "bidirectional"))
    )
    (net (code "45") (name "/FLASH_D3_NR") (class "Default")
      (node (ref "R28") (pin "1") (pinfunction "1_1") (pintype "passive"))
      (node (ref "R29") (pin "2") (pinfunction "2_2") (pintype "passive"))
      (node (ref "U6") (pin "7") (pinfunction "~{HOLD}/RESET(IO3)_7") (pintype "bidirectional"))
    )
    (net (code "46") (name "/FPGA_CLK") (class "Default")
      (node (ref "U1") (pin "N14") (pinfunction "IO_L12P_T1_MRCC_14_N14") (pintype "bidirectional"))
      (node (ref "X1") (pin "3") (pinfunction "OUT_3") (pintype "output"))
    )
    (net (code "47") (name "/INIT_B") (class "Default")
      (node (ref "R13") (pin "1") (pinfunction "1_1") (pintype "passive"))
      (node (ref "U1") (pin "K10") (pinfunction "INIT_B_0_K10") (pintype "bidirectional"))
    )
    (net (code "48") (name "/LED_B") (class "Default")
      (node (ref "U1") (pin "R1") (pinfunction "IO_L7N_T1_34_R1") (pintype "bidirectional"))
      (node (ref "U1") (pin "R2") (pinfunction "IO_L7P_T1_34_R2") (pintype "bidirectional"))
    )
    (net (code "49") (name "/LED_FAULT") (class "Default")
      (node (ref "U1") (pin "N6") (pinfunction "IO_L19N_T3_A09_D25_VREF_14_N6") (pintype "bidirectional"))
    )
    (net (code "50") (name "/LED_G") (class "Default")
      (node (ref "U1") (pin "M1") (pinfunction "IO_L2N_T0_34_M1") (pintype "bidirectional"))
      (node (ref "U1") (pin "M2") (pinfunction "IO_L2P_T0_34_M2") (pintype "bidirectional"))
    )
    (net (code "51") (name "/LED_IR") (class "Default")
      (node (ref "R7") (pin "1") (pinfunction "1_1") (pintype "passive"))
      (node (ref "U1") (pin "P6") (pinfunction "IO_25_14_P6") (pintype "bidirectional"))
    )
    (net (code "52") (name "/LED_R") (class "Default")
      (node (ref "U1") (pin "N1") (pinfunction "IO_L4P_T0_34_N1") (pintype "bidirectional"))
      (node (ref "U1") (pin "N2") (pinfunction "IO_L3N_T0_DQS_34_N2") (pintype "bidirectional"))
    )
    (net (code "53") (name "/LED_USER") (class "Default")
      (node (ref "D5") (pin "2") (pinfunction "A_2") (pintype "passive"))
      (node (ref "U1") (pin "N4") (pinfunction "IO_L6N_T0_VREF_34_N4") (pintype "bidirectional"))
    )
    (net (code "54") (name "/MODE_0") (class "Default")
      (node (ref "R14") (pin "2") (pinfunction "2_2") (pintype "passive"))
      (node (ref "U1") (pin "M9") (pinfunction "M0_0_M9") (pintype "input"))
    )
    (net (code "55") (name "/MODE_1") (class "Default")
      (node (ref "R15") (pin "2") (pinfunction "2_2") (pintype "passive"))
      (node (ref "U1") (pin "M10") (pinfunction "M1_0_M10") (pintype "input"))
    )
    (net (code "56") (name "/MODE_2") (class "Default")
      (node (ref "R16") (pin "2") (pinfunction "2_2") (pintype "passive"))
      (node (ref "U1") (pin "M11") (pinfunction "M2_0_M11") (pintype "input"))
    )
    (net (code "57") (name "/PROGRAM_B") (class "Default")
      (node (ref "R12") (pin "1") (pinfunction "1_1") (pintype "passive"))
      (node (ref "U1") (pin "L9") (pinfunction "PROGRAM_B_0_L9") (pintype "input"))
    )
    (net (code "58") (name "/PUDC_B") (class "Default")
      (node (ref "R76") (pin "1") (pinfunction "1_1") (pintype "passive"))
      (node (ref "U1") (pin "L15") (pinfunction "IO_L3P_T0_DQS_PUDC_B_14_L15") (pintype "bidirectional"))
    )
    (net (code "59") (name "/PWR_12V_OFF") (class "Default")
      (node (ref "U1") (pin "N16") (pinfunction "IO_L7N_T1_D10_14_N16") (pintype "bidirectional"))
    )
    (net (code "60") (name "/RIO_CS") (class "Default")
      (node (ref "U1") (pin "T15") (pinfunction "IO_L10N_T1_D15_14_T15") (pintype "bidirectional"))
    )
    (net (code "61") (name "/RIO_MISO") (class "Default")
      (node (ref "U1") (pin "R15") (pinfunction "IO_L9P_T1_DQS_14_R15") (pintype "bidirectional"))
    )
    (net (code "62") (name "/RIO_MOSI") (class "Default")
      (node (ref "U1") (pin "R16") (pinfunction "IO_L9N_T1_DQS_D13_14_R16") (pintype "bidirectional"))
    )
    (net (code "63") (name "/RIO_SCLK") (class "Default")
      (node (ref "U1") (pin "P14") (pinfunction "IO_L12N_T1_MRCC_14_P14") (pintype "bidirectional"))
    )
    (net (code "64") (name "/USB_CLKOUT") (class "Default")
      (node (ref "U1") (pin "D13") (pinfunction "IO_L12P_T1_MRCC_15_D13") (pintype "bidirectional"))
    )
    (net (code "65") (name "/USB_D0") (class "Default")
      (node (ref "U1") (pin "A15") (pinfunction "IO_L9N_T1_DQS_AD3N_15_A15") (pintype "bidirectional"))
    )
    (net (code "66") (name "/USB_D1") (class "Default")
      (node (ref "U1") (pin "B16") (pinfunction "IO_L10N_T1_AD11N_15_B16") (pintype "bidirectional"))
    )
    (net (code "67") (name "/USB_D2") (class "Default")
      (node (ref "U1") (pin "B15") (pinfunction "IO_L9P_T1_DQS_AD3P_15_B15") (pintype "bidirectional"))
    )
    (net (code "68") (name "/USB_D3") (class "Default")
      (node (ref "U1") (pin "C16") (pinfunction "IO_L10P_T1_AD11P_15_C16") (pintype "bidirectional"))
    )
    (net (code "69") (name "/USB_D4") (class "Default")
      (node (ref "U1") (pin "D16") (pinfunction "IO_L17N_T2_A25_15_D16") (pintype "bidirectional"))
    )
    (net (code "70") (name "/USB_D5") (class "Default")
      (node (ref "U1") (pin "D15") (pinfunction "IO_L15N_T2_DQS_ADV_B_15_D15") (pintype "bidirectional"))
    )
    (net (code "71") (name "/USB_D6") (class "Default")
      (node (ref "U1") (pin "E16") (pinfunction "IO_L17P_T2_A26_15_E16") (pintype "bidirectional"))
    )
    (net (code "72") (name "/USB_D7") (class "Default")
      (node (ref "U1") (pin "E15") (pinfunction "IO_L18N_T2_A23_15_E15") (pintype "bidirectional"))
    )
    (net (code "73") (name "/USB_OE") (class "Default")
      (node (ref "U1") (pin "J15") (pinfunction "IO_L23P_T3_FOE_B_15_J15") (pintype "bidirectional"))
    )
    (net (code "74") (name "/USB_PWREN") (class "Default")
      (node (ref "U1") (pin "B14") (pinfunction "IO_L8N_T1_AD10N_15_B14") (pintype "bidirectional"))
    )
    (net (code "75") (name "/USB_RD") (class "Default")
      (node (ref "U1") (pin "G15") (pinfunction "IO_L24N_T3_RS0_15_G15") (pintype "bidirectional"))
    )
    (net (code "76") (name "/USB_RXF") (class "Default")
      (node (ref "U1") (pin "F15") (pinfunction "IO_L18P_T2_A24_15_F15") (pintype "bidirectional"))
    )
    (net (code "77") (name "/USB_SIWU") (class "Default")
      (node (ref "U1") (pin "J16") (pinfunction "IO_L23N_T3_FWE_B_15_J16") (pintype "bidirectional"))
    )
    (net (code "78") (name "/USB_SUS") (class "Default")
      (node (ref "U1") (pin "H14") (pinfunction "IO_L24P_T3_RS1_15_H14") (pintype "bidirectional"))
    )
    (net (code "79") (name "/USB_TCK") (class "Default")
      (node (ref "U1") (pin "L7") (pinfunction "TCK_0_L7") (pintype "input"))
    )
    (net (code "80") (name "/USB_TDI") (class "Default")
      (node (ref "U1") (pin "N7") (pinfunction "TDI_0_N7") (pintype "input"))
    )
    (net (code "81") (name "/USB_TDO") (class "Default")
      (node (ref "U1") (pin "N8") (pinfunction "TDO_0_N8") (pintype "output"))
    )
    (net (code "82") (name "/USB_TMS") (class "Default")
      (node (ref "U1") (pin "M7") (pinfunction "TMS_0_M7") (pintype "input"))
    )
    (net (code "83") (name "/USB_TXE") (class "Default")
      (node (ref "U1") (pin "G16") (pinfunction "IO_L22N_T3_A16_15_G16") (pintype "bidirectional"))
    )
    (net (code "84") (name "/USB_WR") (class "Default")
      (node (ref "U1") (pin "H16") (pinfunction "IO_L22P_T3_A17_15_H16") (pintype "bidirectional"))
    )
    (net (code "85") (name "AGND") (class "Default")
      (node (ref "C1") (pin "2") (pinfunction "2_2") (pintype "passive"))
      (node (ref "FB2") (pin "2") (pinfunction "2_2") (pintype "passive"))
      (node (ref "U1") (pin "G7") (pinfunction "GNDADC_0_G7") (pintype "power_in"))
      (node (ref "U1") (pin "H7") (pinfunction "VREFN_0_H7") (pintype "input"))
      (node (ref "U1") (pin "H8") (pinfunction "VP_0_H8") (pintype "input"))
      (node (ref "U1") (pin "J7") (pinfunction "VN_0_J7") (pintype "input"))
      (node (ref "U1") (pin "J8") (pinfunction "VREFP_0_J8") (pintype "input"))
    )
    (net (code "86") (name "GND") (class "Default")
      (node (ref "C17") (pin "1") (pinfunction "1_1") (pintype "passive"))
      (node (ref "C18") (pin "1") (pinfunction "1_1") (pintype "passive"))
      (node (ref "C19") (pin "2") (pinfunction "2_2") (pintype "passive"))
      (node (ref "C20") (pin "2") (pinfunction "2_2") (pintype "passive"))
      (node (ref "C21") (pin "2") (pinfunction "2_2") (pintype "passive"))
      (node (ref "C22") (pin "2") (pinfunction "2_2") (pintype "passive"))
      (node (ref "C23") (pin "2") (pinfunction "2_2") (pintype "passive"))
      (node (ref "C24") (pin "2") (pinfunction "2_2") (pintype "passive"))
      (node (ref "C25") (pin "N") (pintype "passive"))
      (node (ref "C26") (pin "2") (pinfunction "2_2") (pintype "passive"))
      (node (ref "C27") (pin "2") (pinfunction "2_2") (pintype "passive"))
      (node (ref "C28") (pin "2") (pinfunction "2_2") (pintype "passive"))
      (node (ref "C29") (pin "2") (pinfunction "2_2") (pintype "passive"))
      (node (ref "C30") (pin "2") (pinfunction "2_2") (pintype "passive"))
      (node (ref "C31") (pin "N") (pintype "passive"))
      (node (ref "C32") (pin "2") (pinfunction "2_2") (pintype "passive"))
      (node (ref "C33") (pin "2") (pinfunction "2_2") (pintype "passive"))
      (node (ref "C36") (pin "2") (pinfunction "2_2") (pintype "passive"))
      (node (ref "C37") (pin "2") (pinfunction "2_2") (pintype "passive"))
      (node (ref "C38") (pin "2") (pinfunction "2_2") (pintype "passive"))
      (node (ref "C39") (pin "2") (pinfunction "2_2") (pintype "passive"))
      (node (ref "C40") (pin "2") (pinfunction "2_2") (pintype "passive"))
      (node (ref "C41") (pin "2") (pinfunction "2_2") (pintype "passive"))
      (node (ref "C42") (pin "2") (pinfunction "2_2") (pintype "passive"))
      (node (ref "C43") (pin "2") (pinfunction "2_2") (pintype "passive"))
      (node (ref "C44") (pin "2") (pinfunction "2_2") (pintype "passive"))
      (node (ref "C45") (pin "2") (pinfunction "2_2") (pintype "passive"))
      (node (ref "C46") (pin "2") (pinfunction "2_2") (pintype "passive"))
      (node (ref "C47") (pin "2") (pinfunction "2_2") (pintype "passive"))
      (node (ref "C49") (pin "2") (pinfunction "2_2") (pintype "passive"))
      (node (ref "C50") (pin "2") (pinfunction "2_2") (pintype "passive"))
      (node (ref "C51") (pin "2") (pinfunction "2_2") (pintype "passive"))
      (node (ref "C52") (pin "2") (pinfunction "2_2") (pintype "passive"))
      (node (ref "C53") (pin "2") (pinfunction "2_2") (pintype "passive"))
      (node (ref "C54") (pin "2") (pinfunction "2_2") (pintype "passive"))
      (node (ref "C55") (pin "2") (pinfunction "2_2") (pintype "passive"))
      (node (ref "C56") (pin "2") (pinfunction "2_2") (pintype "passive"))
      (node (ref "C57") (pin "2") (pinfunction "2_2") (pintype "passive"))
      (node (ref "C58") (pin "2") (pinfunction "2_2") (pintype "passive"))
      (node (ref "C59") (pin "2") (pinfunction "2_2") (pintype "passive"))
      (node (ref "C60") (pin "2") (pinfunction "2_2") (pintype "passive"))
      (node (ref "C61") (pin "2") (pinfunction "2_2") (pintype "passive"))
      (node (ref "C81") (pin "1") (pinfunction "1_1") (pintype "passive"))
      (node (ref "C83") (pin "2") (pinfunction "2_2") (pintype "passive"))
      (node (ref "D6") (pin "1") (pinfunction "C_1") (pintype "passive"))
      (node (ref "FB2") (pin "1") (pinfunction "1_1") (pintype "passive"))
      (node (ref "R15") (pin "1") (pinfunction "1_1") (pintype "passive"))
      (node (ref "R16") (pin "1") (pinfunction "1_1") (pintype "passive"))
      (node (ref "R7") (pin "2") (pinfunction "2_2") (pintype "passive"))
      (node (ref "R8") (pin "2") (pinfunction "2_2") (pintype "passive"))
      (node (ref "U1") (pin "A1") (pinfunction "GND_A1") (pintype "power_in"))
      (node (ref "U1") (pin "A11") (pinfunction "GND_A11") (pintype "power_in"))
      (node (ref "U1") (pin "B8") (pinfunction "GND_B8") (pintype "power_in"))
      (node (ref "U1") (pin "C15") (pinfunction "GND_C15") (pintype "power_in"))
      (node (ref "U1") (pin "C5") (pinfunction "GND_C5") (pintype "power_in"))
      (node (ref "U1") (pin "D12") (pinfunction "GND_D12") (pintype "power_in"))
      (node (ref "U1") (pin "D2") (pinfunction "GND_D2") (pintype "power_in"))
      (node (ref "U1") (pin "E9") (pinfunction "GND_E9") (pintype "power_in"))
      (node (ref "U1") (pin "F10") (pinfunction "GND_F10") (pintype "power_in"))
      (node (ref "U1") (pin "F16") (pinfunction "GND_F16") (pintype "power_in"))
      (node (ref "U1") (pin "F6") (pinfunction "GND_F6") (pintype "power_in"))
      (node (ref "U1") (pin "F8") (pinfunction "VCCBATT_0_F8") (pintype "power_in"))
      (node (ref "U1") (pin "G13") (pinfunction "GND_G13") (pintype "power_in"))
      (node (ref "U1") (pin "G3") (pinfunction "GND_G3") (pintype "power_in"))
      (node (ref "U1") (pin "G9") (pinfunction "GND_G9") (pintype "power_in"))
      (node (ref "U1") (pin "H6") (pinfunction "GND_H6") (pintype "power_in"))
      (node (ref "U1") (pin "J11") (pinfunction "GND_J11") (pintype "power_in"))
      (node (ref "U1") (pin "J9") (pinfunction "GND_J9") (pintype "power_in"))
      (node (ref "U1") (pin "K14") (pinfunction "GND_K14") (pintype "power_in"))
      (node (ref "U1") (pin "K4") (pinfunction "GND_K4") (pintype "power_in"))
      (node (ref "U1") (pin "K6") (pinfunction "GND_K6") (pintype "power_in"))
      (node (ref "U1") (pin "K7") (pinfunction "DXN_0_K7") (pintype "input"))
      (node (ref "U1") (pin "K8") (pinfunction "DXP_0_K8") (pintype "input"))
      (node (ref "U1") (pin "L1") (pinfunction "GND_L1") (pintype "power_in"))
      (node (ref "U1") (pin "L11") (pinfunction "GND_L11") (pintype "power_in"))
      (node (ref "U1") (pin "M8") (pinfunction "GND_M8") (pintype "power_in"))
      (node (ref "U1") (pin "N15") (pinfunction "GND_N15") (pintype "power_in"))
      (node (ref "U1") (pin "N5") (pinfunction "GND_N5") (pintype "power_in"))
      (node (ref "U1") (pin "P12") (pinfunction "GND_P12") (pintype "power_in"))
      (node (ref "U1") (pin "P2") (pinfunction "GND_P2") (pintype "power_in"))
      (node (ref "U1") (pin "R9") (pinfunction "GND_R9") (pintype "power_in"))
      (node (ref "U1") (pin "T16") (pinfunction "GND_T16") (pintype "power_in"))
      (node (ref "U1") (pin "T6") (pinfunction "GND_T6") (pintype "power_in"))
      (node (ref "U6") (pin "4") (pinfunction "GND_4") (pintype "power_in"))
      (node (ref "U6") (pin "9") (pinfunction "EP_9") (pintype "passive"))
      (node (ref "U7") (pin "5") (pinfunction "GND_5") (pintype "input"))
      (node (ref "U7") (pin "9") (pinfunction "EPAD_9") (pintype "power_in"))
      (node (ref "X1") (pin "2") (pinfunction "GND_2") (pintype "power_in"))
    )
    (net (code "87") (name "Net-(D5-C)") (class "Default")
      (node (ref "D5") (pin "1") (pinfunction "C_1") (pintype "passive"))
      (node (ref "R8") (pin "1") (pinfunction "1_1") (pintype "passive"))
    )
    (net (code "88") (name "Net-(D6-A)") (class "Default")
      (node (ref "D6") (pin "2") (pinfunction "A_2") (pintype "passive"))
      (node (ref "R10") (pin "2") (pinfunction "2_2") (pintype "passive"))
    )
    (net (code "89") (name "Net-(X1-OE)") (class "Default")
      (node (ref "R5") (pin "1") (pinfunction "1_1") (pintype "passive"))
      (node (ref "X1") (pin "1") (pinfunction "OE_1") (pintype "input"))
    )
    (net (code "90") (name "VCCADC") (class "Default")
      (node (ref "C1") (pin "1") (pinfunction "1_1") (pintype "passive"))
      (node (ref "C18") (pin "2") (pinfunction "2_2") (pintype "passive"))
      (node (ref "FB1") (pin "1") (pinfunction "1_1") (pintype "passive"))
      (node (ref "U1") (pin "G8") (pinfunction "VCCADC_0_G8") (pintype "power_in"))
    )
    (net (code "91") (name "unconnected-(U1A-IO_0_14-PadK12)") (class "Default")
      (node (ref "U1") (pin "K12") (pinfunction "IO_0_14_K12") (pintype "bidirectional"))
    )
    (net (code "92") (name "unconnected-(U1A-IO_L3N_T0_DQS_EMCCLK_14-PadM15)") (class "Default")
      (node (ref "U1") (pin "M15") (pinfunction "IO_L3N_T0_DQS_EMCCLK_14_M15") (pintype "bidirectional+no_connect"))
    )
    (net (code "93") (name "unconnected-(U1A-IO_L4P_T0_D04_14-PadL14)") (class "Default")
      (node (ref "U1") (pin "L14") (pinfunction "IO_L4P_T0_D04_14_L14") (pintype "bidirectional"))
    )
    (net (code "94") (name "unconnected-(U1A-IO_L5N_T0_D07_14-PadL13)") (class "Default")
      (node (ref "U1") (pin "L13") (pinfunction "IO_L5N_T0_D07_14_L13") (pintype "bidirectional"))
    )
    (net (code "95") (name "unconnected-(U1A-IO_L5P_T0_D06_14-PadK13)") (class "Default")
      (node (ref "U1") (pin "K13") (pinfunction "IO_L5P_T0_D06_14_K13") (pintype "bidirectional"))
    )
    (net (code "96") (name "unconnected-(U1A-IO_L6N_T0_D08_VREF_14-PadM12)") (class "Default")
      (node (ref "U1") (pin "M12") (pinfunction "IO_L6N_T0_D08_VREF_14_M12") (pintype "bidirectional"))
    )
    (net (code "97") (name "unconnected-(U1A-IO_L7P_T1_D09_14-PadM16)") (class "Default")
      (node (ref "U1") (pin "M16") (pinfunction "IO_L7P_T1_D09_14_M16") (pintype "bidirectional"))
    )
    (net (code "98") (name "unconnected-(U1A-IO_L8N_T1_D12_14-PadP16)") (class "Default")
      (node (ref "U1") (pin "P16") (pinfunction "IO_L8N_T1_D12_14_P16") (pintype "bidirectional"))
    )
    (net (code "99") (name "unconnected-(U1A-IO_L8P_T1_D11_14-PadP15)") (class "Default")
      (node (ref "U1") (pin "P15") (pinfunction "IO_L8P_T1_D11_14_P15") (pintype "bidirectional"))
    )
    (net (code "100") (name "unconnected-(U1A-IO_L10P_T1_D14_14-PadT14)") (class "Default")
      (node (ref "U1") (pin "T14") (pinfunction "IO_L10P_T1_D14_14_T14") (pintype "bidirectional"))
    )
    (net (code "101") (name "unconnected-(U1A-IO_L11N_T1_SRCC_14-PadP13)") (class "Default")
      (node (ref "U1") (pin "P13") (pinfunction "IO_L11N_T1_SRCC_14_P13") (pintype "bidirectional"))
    )
    (net (code "102") (name "unconnected-(U1A-IO_L11P_T1_SRCC_14-PadN13)") (class "Default")
      (node (ref "U1") (pin "N13") (pinfunction "IO_L11P_T1_SRCC_14_N13") (pintype "bidirectional"))
    )
    (net (code "103") (name "unconnected-(U1A-IO_L13N_T2_MRCC_14-PadN12)") (class "Default")
      (node (ref "U1") (pin "N12") (pinfunction "IO_L13N_T2_MRCC_14_N12") (pintype "bidirectional"))
    )
    (net (code "104") (name "unconnected-(U1A-IO_L13P_T2_MRCC_14-PadN11)") (class "Default")
      (node (ref "U1") (pin "N11") (pinfunction "IO_L13P_T2_MRCC_14_N11") (pintype "bidirectional"))
    )
    (net (code "105") (name "unconnected-(U1A-IO_L14P_T2_SRCC_14-PadP10)") (class "Default")
      (node (ref "U1") (pin "P10") (pinfunction "IO_L14P_T2_SRCC_14_P10") (pintype "bidirectional"))
    )
    (net (code "106") (name "unconnected-(U1A-IO_L15N_T2_DQS_DOUT_CSO_B_14-PadT12)") (class "Default")
      (node (ref "U1") (pin "T12") (pinfunction "IO_L15N_T2_DQS_DOUT_CSO_B_14_T12") (pintype "bidirectional"))
    )
    (net (code "107") (name "unconnected-(U1A-IO_L15P_T2_DQS_RDWR_B_14-PadR12)") (class "Default")
      (node (ref "U1") (pin "R12") (pinfunction "IO_L15P_T2_DQS_RDWR_B_14_R12") (pintype "bidirectional"))
    )
    (net (code "108") (name "unconnected-(U1A-IO_L16N_T2_A15_D31_14-PadT13)") (class "Default")
      (node (ref "U1") (pin "T13") (pinfunction "IO_L16N_T2_A15_D31_14_T13") (pintype "bidirectional"))
    )
    (net (code "109") (name "unconnected-(U1A-IO_L18N_T2_A11_D27_14-PadP9)") (class "Default")
      (node (ref "U1") (pin "P9") (pinfunction "IO_L18N_T2_A11_D27_14_P9") (pintype "bidirectional"))
    )
    (net (code "110") (name "unconnected-(U1A-IO_L18P_T2_A12_D28_14-PadN9)") (class "Default")
      (node (ref "U1") (pin "N9") (pinfunction "IO_L18P_T2_A12_D28_14_N9") (pintype "bidirectional"))
    )
    (net (code "111") (name "unconnected-(U1A-IO_L19P_T3_A10_D26_14-PadM6)") (class "Default")
      (node (ref "U1") (pin "M6") (pinfunction "IO_L19P_T3_A10_D26_14_M6") (pintype "bidirectional"))
    )
    (net (code "112") (name "unconnected-(U1A-IO_L20N_T3_A07_D23_14-PadR8)") (class "Default")
      (node (ref "U1") (pin "R8") (pinfunction "IO_L20N_T3_A07_D23_14_R8") (pintype "bidirectional"))
    )
    (net (code "113") (name "unconnected-(U1A-IO_L20P_T3_A08_D24_14-PadP8)") (class "Default")
      (node (ref "U1") (pin "P8") (pinfunction "IO_L20P_T3_A08_D24_14_P8") (pintype "bidirectional"))
    )
    (net (code "114") (name "unconnected-(U1A-IO_L23N_T3_A02_D18_14-PadT5)") (class "Default")
      (node (ref "U1") (pin "T5") (pinfunction "IO_L23N_T3_A02_D18_14_T5") (pintype "bidirectional"))
    )
    (net (code "115") (name "unconnected-(U1A-IO_L24N_T3_A00_D16_14-PadR7)") (class "Default")
      (node (ref "U1") (pin "R7") (pinfunction "IO_L24N_T3_A00_D16_14_R7") (pintype "bidirectional"))
    )
    (net (code "116") (name "unconnected-(U1B-IO_0_15-PadD10)") (class "Default")
      (node (ref "U1") (pin "D10") (pinfunction "IO_0_15_D10") (pintype "bidirectional"))
    )
    (net (code "117") (name "unconnected-(U1B-IO_25_15-PadG11)") (class "Default")
      (node (ref "U1") (pin "G11") (pinfunction "IO_25_15_G11") (pintype "bidirectional"))
    )
    (net (code "118") (name "unconnected-(U1B-IO_L1N_T0_AD0N_15-PadC9)") (class "Default")
      (node (ref "U1") (pin "C9") (pinfunction "IO_L1N_T0_AD0N_15_C9") (pintype "bidirectional"))
    )
    (net (code "119") (name "unconnected-(U1B-IO_L1P_T0_AD0P_15-PadC8)") (class "Default")
      (node (ref "U1") (pin "C8") (pinfunction "IO_L1P_T0_AD0P_15_C8") (pintype "bidirectional"))
    )
    (net (code "120") (name "unconnected-(U1B-IO_L2N_T0_AD8N_15-PadA9)") (class "Default")
      (node (ref "U1") (pin "A9") (pinfunction "IO_L2N_T0_AD8N_15_A9") (pintype "bidirectional"))
    )
    (net (code "121") (name "unconnected-(U1B-IO_L2P_T0_AD8P_15-PadA8)") (class "Default")
      (node (ref "U1") (pin "A8") (pinfunction "IO_L2P_T0_AD8P_15_A8") (pintype "bidirectional"))
    )
    (net (code "122") (name "unconnected-(U1B-IO_L3P_T0_DQS_AD1P_15-PadB9)") (class "Default")
      (node (ref "U1") (pin "B9") (pinfunction "IO_L3P_T0_DQS_AD1P_15_B9") (pintype "bidirectional"))
    )
    (net (code "123") (name "unconnected-(U1B-IO_L4N_T0_15-PadB11)") (class "Default")
      (node (ref "U1") (pin "B11") (pinfunction "IO_L4N_T0_15_B11") (pintype "bidirectional"))
    )
    (net (code "124") (name "unconnected-(U1B-IO_L4P_T0_15-PadB10)") (class "Default")
      (node (ref "U1") (pin "B10") (pinfunction "IO_L4P_T0_15_B10") (pintype "bidirectional"))
    )
    (net (code "125") (name "unconnected-(U1B-IO_L5P_T0_AD9P_15-PadB12)") (class "Default")
      (node (ref "U1") (pin "B12") (pinfunction "IO_L5P_T0_AD9P_15_B12") (pintype "bidirectional"))
    )
    (net (code "126") (name "unconnected-(U1B-IO_L6N_T0_VREF_15-PadD9)") (class "Default")
      (node (ref "U1") (pin "D9") (pinfunction "IO_L6N_T0_VREF_15_D9") (pintype "bidirectional"))
    )
    (net (code "127") (name "unconnected-(U1B-IO_L6P_T0_15-PadD8)") (class "Default")
      (node (ref "U1") (pin "D8") (pinfunction "IO_L6P_T0_15_D8") (pintype "bidirectional"))
    )
    (net (code "128") (name "unconnected-(U1B-IO_L7N_T1_AD2N_15-PadA14)") (class "Default")
      (node (ref "U1") (pin "A14") (pinfunction "IO_L7N_T1_AD2N_15_A14") (pintype "bidirectional"))
    )
    (net (code "129") (name "unconnected-(U1B-IO_L8P_T1_AD10P_15-PadC14)") (class "Default")
      (node (ref "U1") (pin "C14") (pinfunction "IO_L8P_T1_AD10P_15_C14") (pintype "bidirectional"))
    )
    (net (code "130") (name "unconnected-(U1B-IO_L11N_T1_SRCC_15-PadC12)") (class "Default")
      (node (ref "U1") (pin "C12") (pinfunction "IO_L11N_T1_SRCC_15_C12") (pintype "bidirectional"))
    )
    (net (code "131") (name "unconnected-(U1B-IO_L11P_T1_SRCC_15-PadC11)") (class "Default")
      (node (ref "U1") (pin "C11") (pinfunction "IO_L11P_T1_SRCC_15_C11") (pintype "bidirectional"))
    )
    (net (code "132") (name "unconnected-(U1B-IO_L13N_T2_MRCC_15-PadE13)") (class "Default")
      (node (ref "U1") (pin "E13") (pinfunction "IO_L13N_T2_MRCC_15_E13") (pintype "bidirectional"))
    )
    (net (code "133") (name "unconnected-(U1B-IO_L13P_T2_MRCC_15-PadE12)") (class "Default")
      (node (ref "U1") (pin "E12") (pinfunction "IO_L13P_T2_MRCC_15_E12") (pintype "bidirectional"))
    )
    (net (code "134") (name "unconnected-(U1B-IO_L14N_T2_SRCC_15-PadD11)") (class "Default")
      (node (ref "U1") (pin "D11") (pinfunction "IO_L14N_T2_SRCC_15_D11") (pintype "bidirectional"))
    )
    (net (code "135") (name "unconnected-(U1B-IO_L14P_T2_SRCC_15-PadE11)") (class "Default")
      (node (ref "U1") (pin "E11") (pinfunction "IO_L14P_T2_SRCC_15_E11") (pintype "bidirectional"))
    )
    (net (code "136") (name "unconnected-(U1B-IO_L15P_T2_DQS_15-PadD14)") (class "Default")
      (node (ref "U1") (pin "D14") (pinfunction "IO_L15P_T2_DQS_15_D14") (pintype "bidirectional"))
    )
    (net (code "137") (name "unconnected-(U1B-IO_L16N_T2_A27_15-PadF13)") (class "Default")
      (node (ref "U1") (pin "F13") (pinfunction "IO_L16N_T2_A27_15_F13") (pintype "bidirectional"))
    )
    (net (code "138") (name "unconnected-(U1B-IO_L16P_T2_A28_15-PadF12)") (class "Default")
      (node (ref "U1") (pin "F12") (pinfunction "IO_L16P_T2_A28_15_F12") (pintype "bidirectional"))
    )
    (net (code "139") (name "unconnected-(U1B-IO_L19N_T3_A21_VREF_15-PadG12)") (class "Default")
      (node (ref "U1") (pin "G12") (pinfunction "IO_L19N_T3_A21_VREF_15_G12") (pintype "bidirectional"))
    )
    (net (code "140") (name "unconnected-(U1B-IO_L19P_T3_A22_15-PadH11)") (class "Default")
      (node (ref "U1") (pin "H11") (pinfunction "IO_L19P_T3_A22_15_H11") (pintype "bidirectional"))
    )
    (net (code "141") (name "unconnected-(U1B-IO_L20N_T3_A19_15-PadH13)") (class "Default")
      (node (ref "U1") (pin "H13") (pinfunction "IO_L20N_T3_A19_15_H13") (pintype "bidirectional"))
    )
    (net (code "142") (name "unconnected-(U1B-IO_L20P_T3_A20_15-PadH12)") (class "Default")
      (node (ref "U1") (pin "H12") (pinfunction "IO_L20P_T3_A20_15_H12") (pintype "bidirectional"))
    )
    (net (code "143") (name "unconnected-(U1B-IO_L21N_T3_DQS_A18_15-PadF14)") (class "Default")
      (node (ref "U1") (pin "F14") (pinfunction "IO_L21N_T3_DQS_A18_15_F14") (pintype "bidirectional"))
    )
    (net (code "144") (name "unconnected-(U1B-IO_L21P_T3_DQS_15-PadG14)") (class "Default")
      (node (ref "U1") (pin "G14") (pinfunction "IO_L21P_T3_DQS_15_G14") (pintype "bidirectional"))
    )
    (net (code "145") (name "unconnected-(U1C-IO_0_34-PadL5)") (class "Default")
      (node (ref "U1") (pin "L5") (pinfunction "IO_0_34_L5") (pintype "bidirectional"))
    )
    (net (code "146") (name "unconnected-(U1C-IO_L1N_T0_34-PadM4)") (class "Default")
      (node (ref "U1") (pin "M4") (pinfunction "IO_L1N_T0_34_M4") (pintype "bidirectional"))
    )
    (net (code "147") (name "unconnected-(U1C-IO_L1P_T0_34-PadL4)") (class "Default")
      (node (ref "U1") (pin "L4") (pinfunction "IO_L1P_T0_34_L4") (pintype "bidirectional"))
    )
    (net (code "148") (name "unconnected-(U1C-IO_L3P_T0_DQS_34-PadN3)") (class "Default")
      (node (ref "U1") (pin "N3") (pinfunction "IO_L3P_T0_DQS_34_N3") (pintype "bidirectional"))
    )
    (net (code "149") (name "unconnected-(U1C-IO_L4N_T0_34-PadP1)") (class "Default")
      (node (ref "U1") (pin "P1") (pinfunction "IO_L4N_T0_34_P1") (pintype "bidirectional"))
    )
    (net (code "150") (name "unconnected-(U1C-IO_L5N_T0_34-PadP3)") (class "Default")
      (node (ref "U1") (pin "P3") (pinfunction "IO_L5N_T0_34_P3") (pintype "bidirectional"))
    )
    (net (code "151") (name "unconnected-(U1C-IO_L5P_T0_34-PadP4)") (class "Default")
      (node (ref "U1") (pin "P4") (pinfunction "IO_L5P_T0_34_P4") (pintype "bidirectional"))
    )
    (net (code "152") (name "unconnected-(U1C-IO_L6P_T0_34-PadM5)") (class "Default")
      (node (ref "U1") (pin "M5") (pinfunction "IO_L6P_T0_34_M5") (pintype "bidirectional"))
    )
    (net (code "153") (name "unconnected-(U1C-IO_L8N_T1_34-PadT2)") (class "Default")
      (node (ref "U1") (pin "T2") (pinfunction "IO_L8N_T1_34_T2") (pintype "bidirectional"))
    )
    (net (code "154") (name "unconnected-(U1C-IO_L8P_T1_34-PadR3)") (class "Default")
      (node (ref "U1") (pin "R3") (pinfunction "IO_L8P_T1_34_R3") (pintype "bidirectional"))
    )
    (net (code "155") (name "unconnected-(U1C-IO_L9N_T1_DQS_34-PadT3)") (class "Default")
      (node (ref "U1") (pin "T3") (pinfunction "IO_L9N_T1_DQS_34_T3") (pintype "bidirectional"))
    )
    (net (code "156") (name "unconnected-(U1C-IO_L9P_T1_DQS_34-PadT4)") (class "Default")
      (node (ref "U1") (pin "T4") (pinfunction "IO_L9P_T1_DQS_34_T4") (pintype "bidirectional"))
    )
    (net (code "157") (name "unconnected-(U1C-IO_L10P_T1_34-PadP5)") (class "Default")
      (node (ref "U1") (pin "P5") (pinfunction "IO_L10P_T1_34_P5") (pintype "bidirectional"))
    )
    (net (code "158") (name "unconnected-(U1D-IO_0_35-PadE6)") (class "Default")
      (node (ref "U1") (pin "E6") (pinfunction "IO_0_35_E6") (pintype "bidirectional"))
    )
    (net (code "159") (name "unconnected-(U1D-IO_25_35-PadK5)") (class "Default")
      (node (ref "U1") (pin "K5") (pinfunction "IO_25_35_K5") (pintype "bidirectional"))
    )
    (net (code "160") (name "unconnected-(U1D-IO_L1N_T0_AD4N_35-PadA7)") (class "Default")
      (node (ref "U1") (pin "A7") (pinfunction "IO_L1N_T0_AD4N_35_A7") (pintype "bidirectional"))
    )
    (net (code "161") (name "unconnected-(U1D-IO_L1P_T0_AD4P_35-PadB7)") (class "Default")
      (node (ref "U1") (pin "B7") (pinfunction "IO_L1P_T0_AD4P_35_B7") (pintype "bidirectional"))
    )
    (net (code "162") (name "unconnected-(U1D-IO_L2N_T0_AD12N_35-PadB5)") (class "Default")
      (node (ref "U1") (pin "B5") (pinfunction "IO_L2N_T0_AD12N_35_B5") (pintype "bidirectional"))
    )
    (net (code "163") (name "unconnected-(U1D-IO_L2P_T0_AD12P_35-PadB6)") (class "Default")
      (node (ref "U1") (pin "B6") (pinfunction "IO_L2P_T0_AD12P_35_B6") (pintype "bidirectional"))
    )
    (net (code "164") (name "unconnected-(U1D-IO_L3N_T0_DQS_AD5N_35-PadA4)") (class "Default")
      (node (ref "U1") (pin "A4") (pinfunction "IO_L3N_T0_DQS_AD5N_35_A4") (pintype "bidirectional"))
    )
    (net (code "165") (name "unconnected-(U1D-IO_L3P_T0_DQS_AD5P_35-PadA5)") (class "Default")
      (node (ref "U1") (pin "A5") (pinfunction "IO_L3P_T0_DQS_AD5P_35_A5") (pintype "bidirectional"))
    )
    (net (code "166") (name "unconnected-(U1D-IO_L4N_T0_35-PadA3)") (class "Default")
      (node (ref "U1") (pin "A3") (pinfunction "IO_L4N_T0_35_A3") (pintype "bidirectional"))
    )
    (net (code "167") (name "unconnected-(U1D-IO_L4P_T0_35-PadB4)") (class "Default")
      (node (ref "U1") (pin "B4") (pinfunction "IO_L4P_T0_35_B4") (pintype "bidirectional"))
    )
    (net (code "168") (name "unconnected-(U1D-IO_L8N_T1_AD14N_35-PadA2)") (class "Default")
      (node (ref "U1") (pin "A2") (pinfunction "IO_L8N_T1_AD14N_35_A2") (pintype "bidirectional"))
    )
    (net (code "169") (name "unconnected-(U1D-IO_L8P_T1_AD14P_35-PadB2)") (class "Default")
      (node (ref "U1") (pin "B2") (pinfunction "IO_L8P_T1_AD14P_35_B2") (pintype "bidirectional"))
    )
    (net (code "170") (name "unconnected-(U1D-IO_L9N_T1_DQS_AD7N_35-PadB1)") (class "Default")
      (node (ref "U1") (pin "B1") (pinfunction "IO_L9N_T1_DQS_AD7N_35_B1") (pintype "bidirectional"))
    )
    (net (code "171") (name "unconnected-(U1D-IO_L9P_T1_DQS_AD7P_35-PadC1)") (class "Default")
      (node (ref "U1") (pin "C1") (pinfunction "IO_L9P_T1_DQS_AD7P_35_C1") (pintype "bidirectional"))
    )
    (net (code "172") (name "unconnected-(U1D-IO_L10N_T1_AD15N_35-PadD1)") (class "Default")
      (node (ref "U1") (pin "D1") (pinfunction "IO_L10N_T1_AD15N_35_D1") (pintype "bidirectional"))
    )
    (net (code "173") (name "unconnected-(U1D-IO_L10P_T1_AD15P_35-PadE2)") (class "Default")
      (node (ref "U1") (pin "E2") (pinfunction "IO_L10P_T1_AD15P_35_E2") (pintype "bidirectional"))
    )
    (net (code "174") (name "unconnected-(U1D-IO_L11N_T1_SRCC_35-PadD3)") (class "Default")
      (node (ref "U1") (pin "D3") (pinfunction "IO_L11N_T1_SRCC_35_D3") (pintype "bidirectional"))
    )
    (net (code "175") (name "unconnected-(U1D-IO_L11P_T1_SRCC_35-PadE3)") (class "Default")
      (node (ref "U1") (pin "E3") (pinfunction "IO_L11P_T1_SRCC_35_E3") (pintype "bidirectional"))
    )
    (net (code "176") (name "unconnected-(U1D-IO_L14N_T2_SRCC_35-PadF3)") (class "Default")
      (node (ref "U1") (pin "F3") (pinfunction "IO_L14N_T2_SRCC_35_F3") (pintype "bidirectional"))
    )
    (net (code "177") (name "unconnected-(U1D-IO_L14P_T2_SRCC_35-PadF4)") (class "Default")
      (node (ref "U1") (pin "F4") (pinfunction "IO_L14P_T2_SRCC_35_F4") (pintype "bidirectional"))
    )
    (net (code "178") (name "unconnected-(U1D-IO_L15N_T2_DQS_35-PadE1)") (class "Default")
      (node (ref "U1") (pin "E1") (pinfunction "IO_L15N_T2_DQS_35_E1") (pintype "bidirectional"))
    )
    (net (code "179") (name "unconnected-(U1D-IO_L15P_T2_DQS_35-PadF2)") (class "Default")
      (node (ref "U1") (pin "F2") (pinfunction "IO_L15P_T2_DQS_35_F2") (pintype "bidirectional"))
    )
    (net (code "180") (name "unconnected-(U1D-IO_L17N_T2_35-PadG1)") (class "Default")
      (node (ref "U1") (pin "G1") (pinfunction "IO_L17N_T2_35_G1") (pintype "bidirectional"))
    )
    (net (code "181") (name "unconnected-(U1D-IO_L17P_T2_35-PadG2)") (class "Default")
      (node (ref "U1") (pin "G2") (pinfunction "IO_L17P_T2_35_G2") (pintype "bidirectional"))
    )
    (net (code "182") (name "unconnected-(U1D-IO_L18N_T2_35-PadH4)") (class "Default")
      (node (ref "U1") (pin "H4") (pinfunction "IO_L18N_T2_35_H4") (pintype "bidirectional"))
    )
    (net (code "183") (name "unconnected-(U1D-IO_L18P_T2_35-PadH5)") (class "Default")
      (node (ref "U1") (pin "H5") (pinfunction "IO_L18P_T2_35_H5") (pintype "bidirectional"))
    )
    (net (code "184") (name "unconnected-(U1D-IO_L19N_T3_VREF_35-PadJ4)") (class "Default")
      (node (ref "U1") (pin "J4") (pinfunction "IO_L19N_T3_VREF_35_J4") (pintype "bidirectional"))
    )
    (net (code "185") (name "unconnected-(U1D-IO_L19P_T3_35-PadJ5)") (class "Default")
      (node (ref "U1") (pin "J5") (pinfunction "IO_L19P_T3_35_J5") (pintype "bidirectional"))
    )
    (net (code "186") (name "unconnected-(U1D-IO_L20N_T3_35-PadH1)") (class "Default")
      (node (ref "U1") (pin "H1") (pinfunction "IO_L20N_T3_35_H1") (pintype "bidirectional"))
    )
    (net (code "187") (name "unconnected-(U1D-IO_L20P_T3_35-PadH2)") (class "Default")
      (node (ref "U1") (pin "H2") (pinfunction "IO_L20P_T3_35_H2") (pintype "bidirectional"))
    )
    (net (code "188") (name "unconnected-(U1D-IO_L21N_T3_DQS_35-PadH3)") (class "Default")
      (node (ref "U1") (pin "H3") (pinfunction "IO_L21N_T3_DQS_35_H3") (pintype "bidirectional"))
    )
    (net (code "189") (name "unconnected-(U1D-IO_L21P_T3_DQS_35-PadJ3)") (class "Default")
      (node (ref "U1") (pin "J3") (pinfunction "IO_L21P_T3_DQS_35_J3") (pintype "bidirectional"))
    )
    (net (code "190") (name "unconnected-(U1D-IO_L22N_T3_35-PadJ1)") (class "Default")
      (node (ref "U1") (pin "J1") (pinfunction "IO_L22N_T3_35_J1") (pintype "bidirectional"))
    )
    (net (code "191") (name "unconnected-(U1D-IO_L22P_T3_35-PadK1)") (class "Default")
      (node (ref "U1") (pin "K1") (pinfunction "IO_L22P_T3_35_K1") (pintype "bidirectional"))
    )
    (net (code "192") (name "unconnected-(U1D-IO_L23N_T3_35-PadL2)") (class "Default")
      (node (ref "U1") (pin "L2") (pinfunction "IO_L23N_T3_35_L2") (pintype "bidirectional"))
    )
    (net (code "193") (name "unconnected-(U1D-IO_L23P_T3_35-PadL3)") (class "Default")
      (node (ref "U1") (pin "L3") (pinfunction "IO_L23P_T3_35_L3") (pintype "bidirectional"))
    )
    (net (code "194") (name "unconnected-(U1D-IO_L24N_T3_35-PadK2)") (class "Default")
      (node (ref "U1") (pin "K2") (pinfunction "IO_L24N_T3_35_K2") (pintype "bidirectional"))
    )
    (net (code "195") (name "unconnected-(U1D-IO_L24P_T3_35-PadK3)") (class "Default")
      (node (ref "U1") (pin "K3") (pinfunction "IO_L24P_T3_35_K3") (pintype "bidirectional"))
    )
    (net (code "196") (name "unconnected-(U7-NC-Pad7)") (class "Default")
      (node (ref "U7") (pin "7") (pinfunction "NC_7") (pintype "input+no_connect"))
    )
  )
)
